# debugger_board.net
KiCad netlist of a schematic drawn in EAGLE
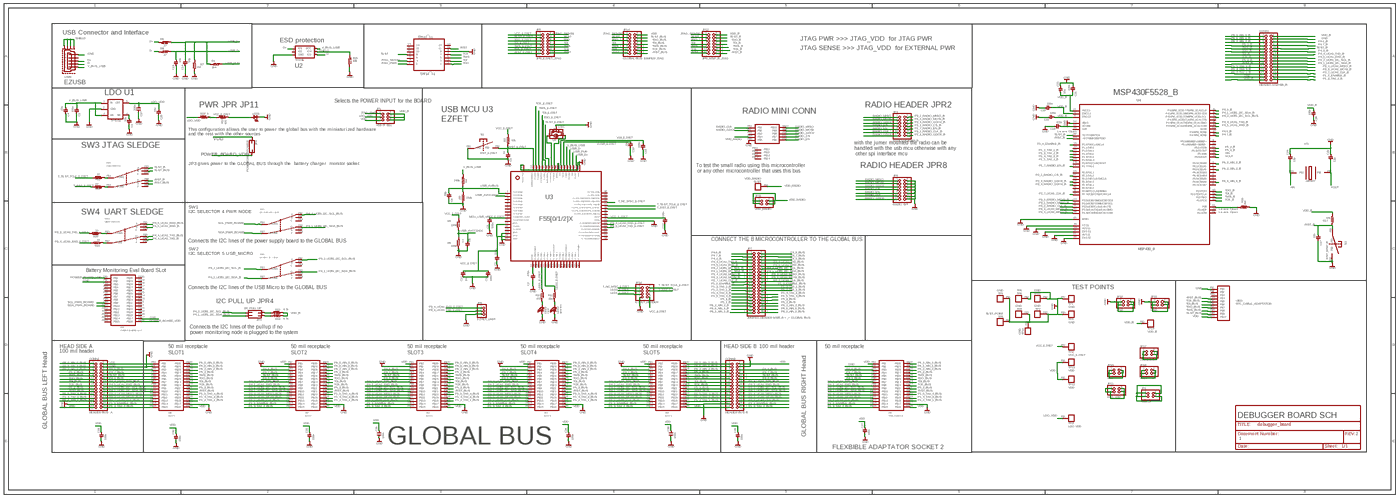
[diagram p0: schematic, sheet 1, overview]
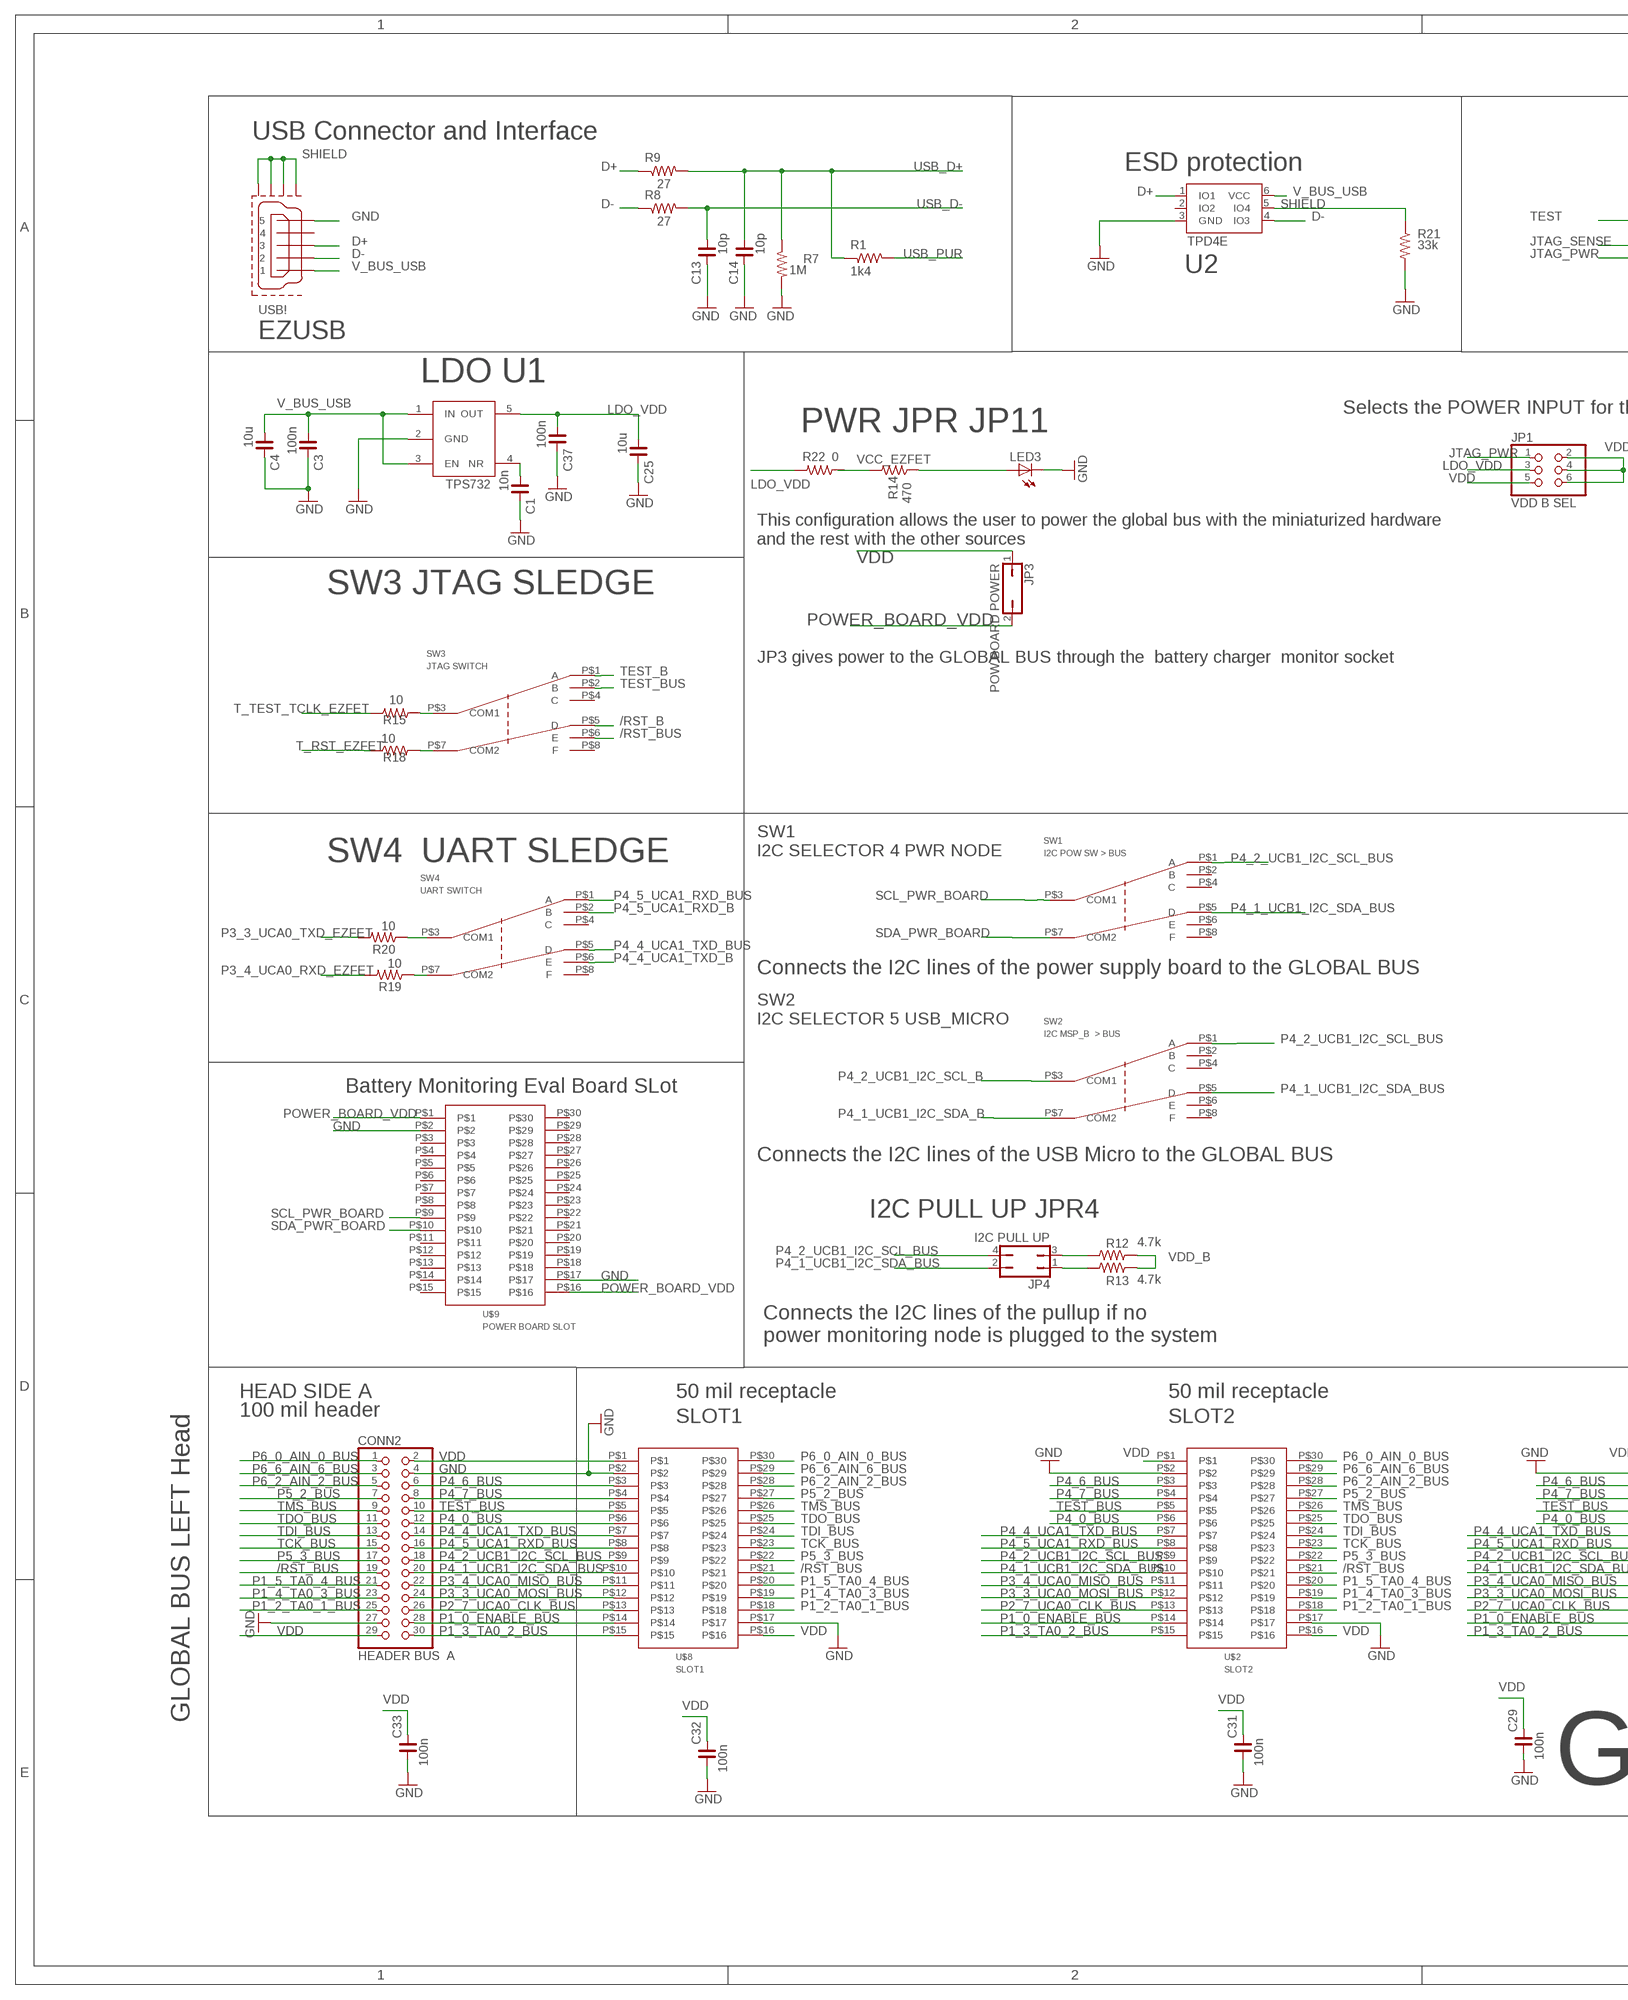
[diagram p1: schematic, sheet 1, part 1 of 4]
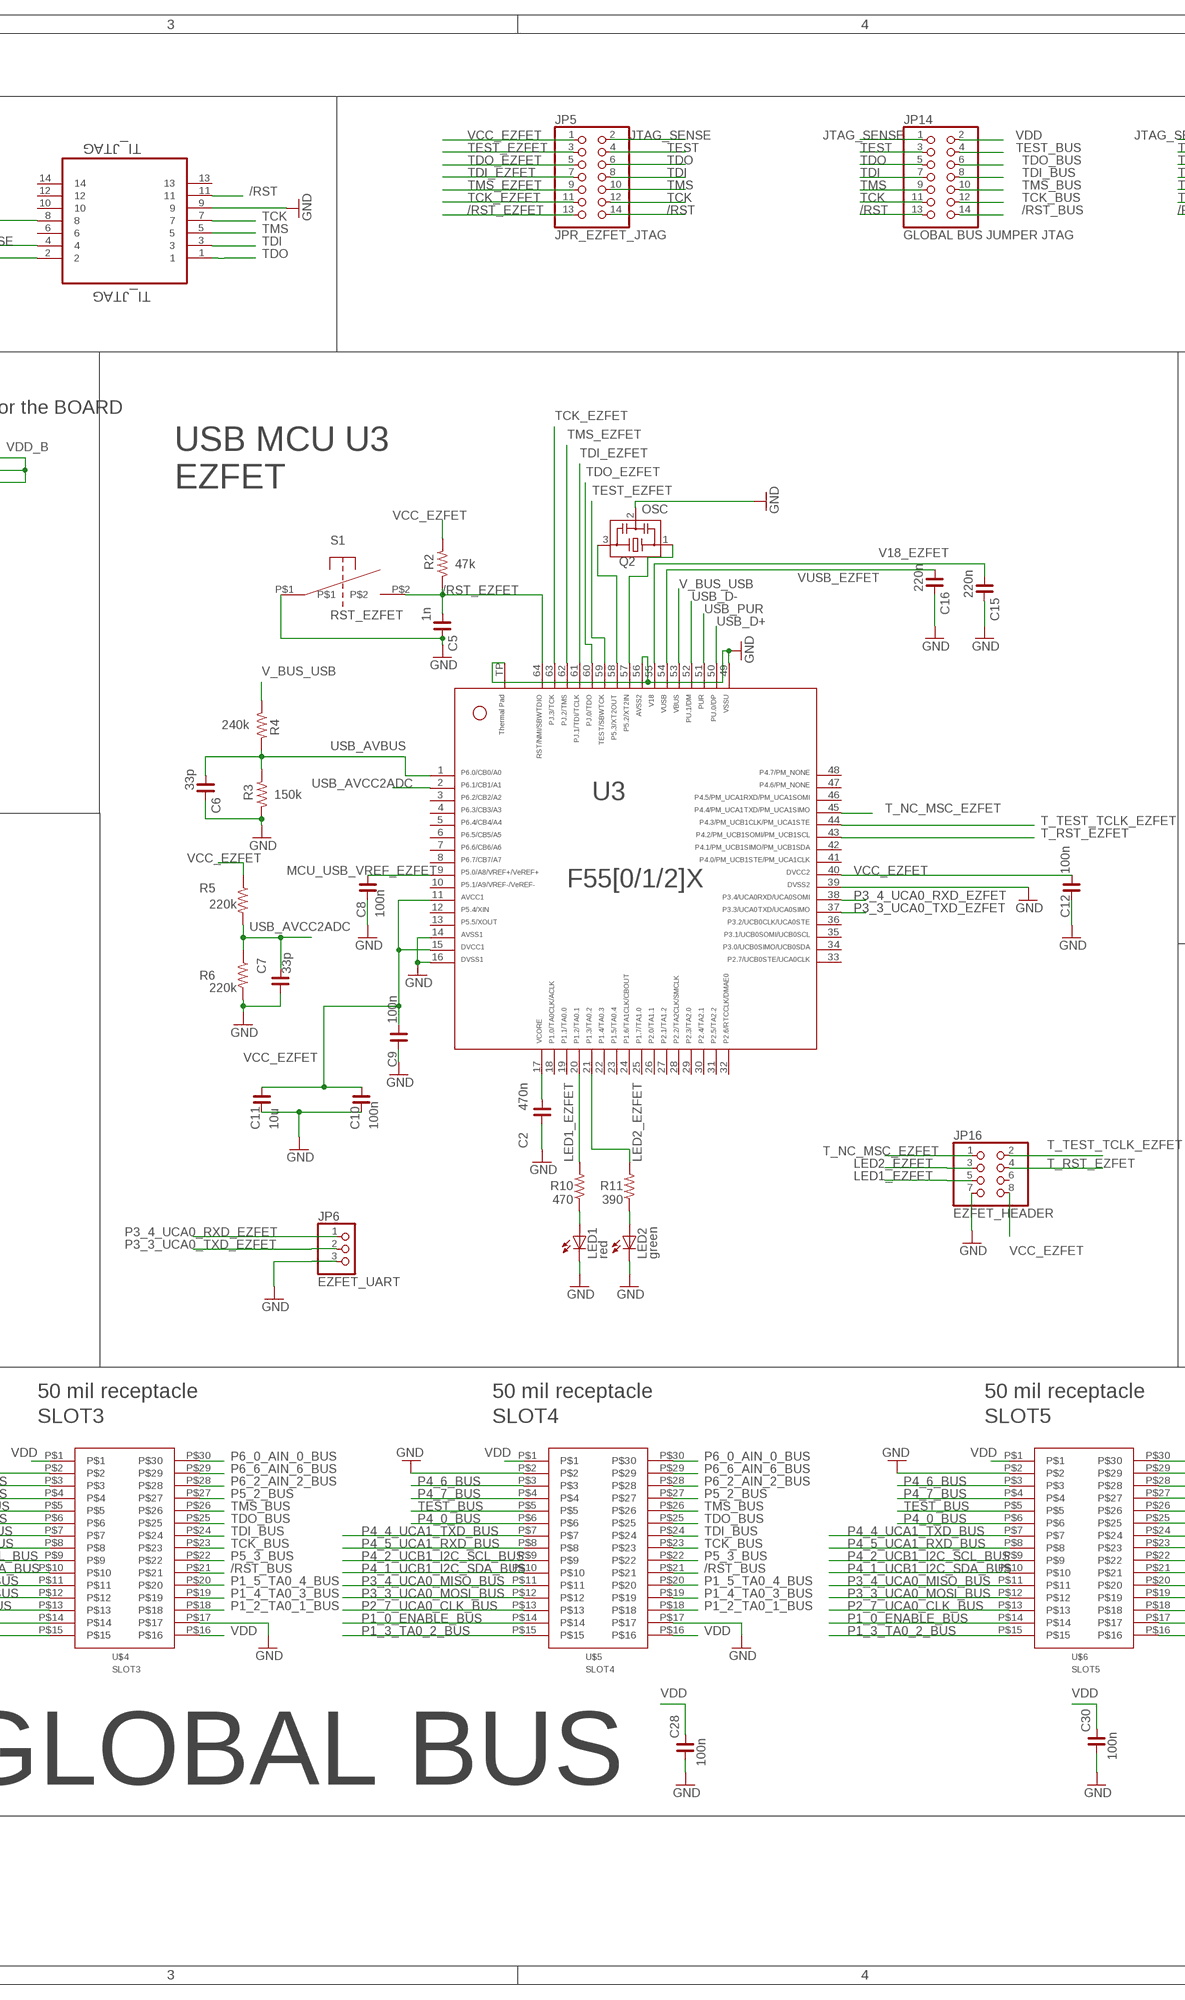
[diagram p2: schematic, sheet 1, part 2 of 4]
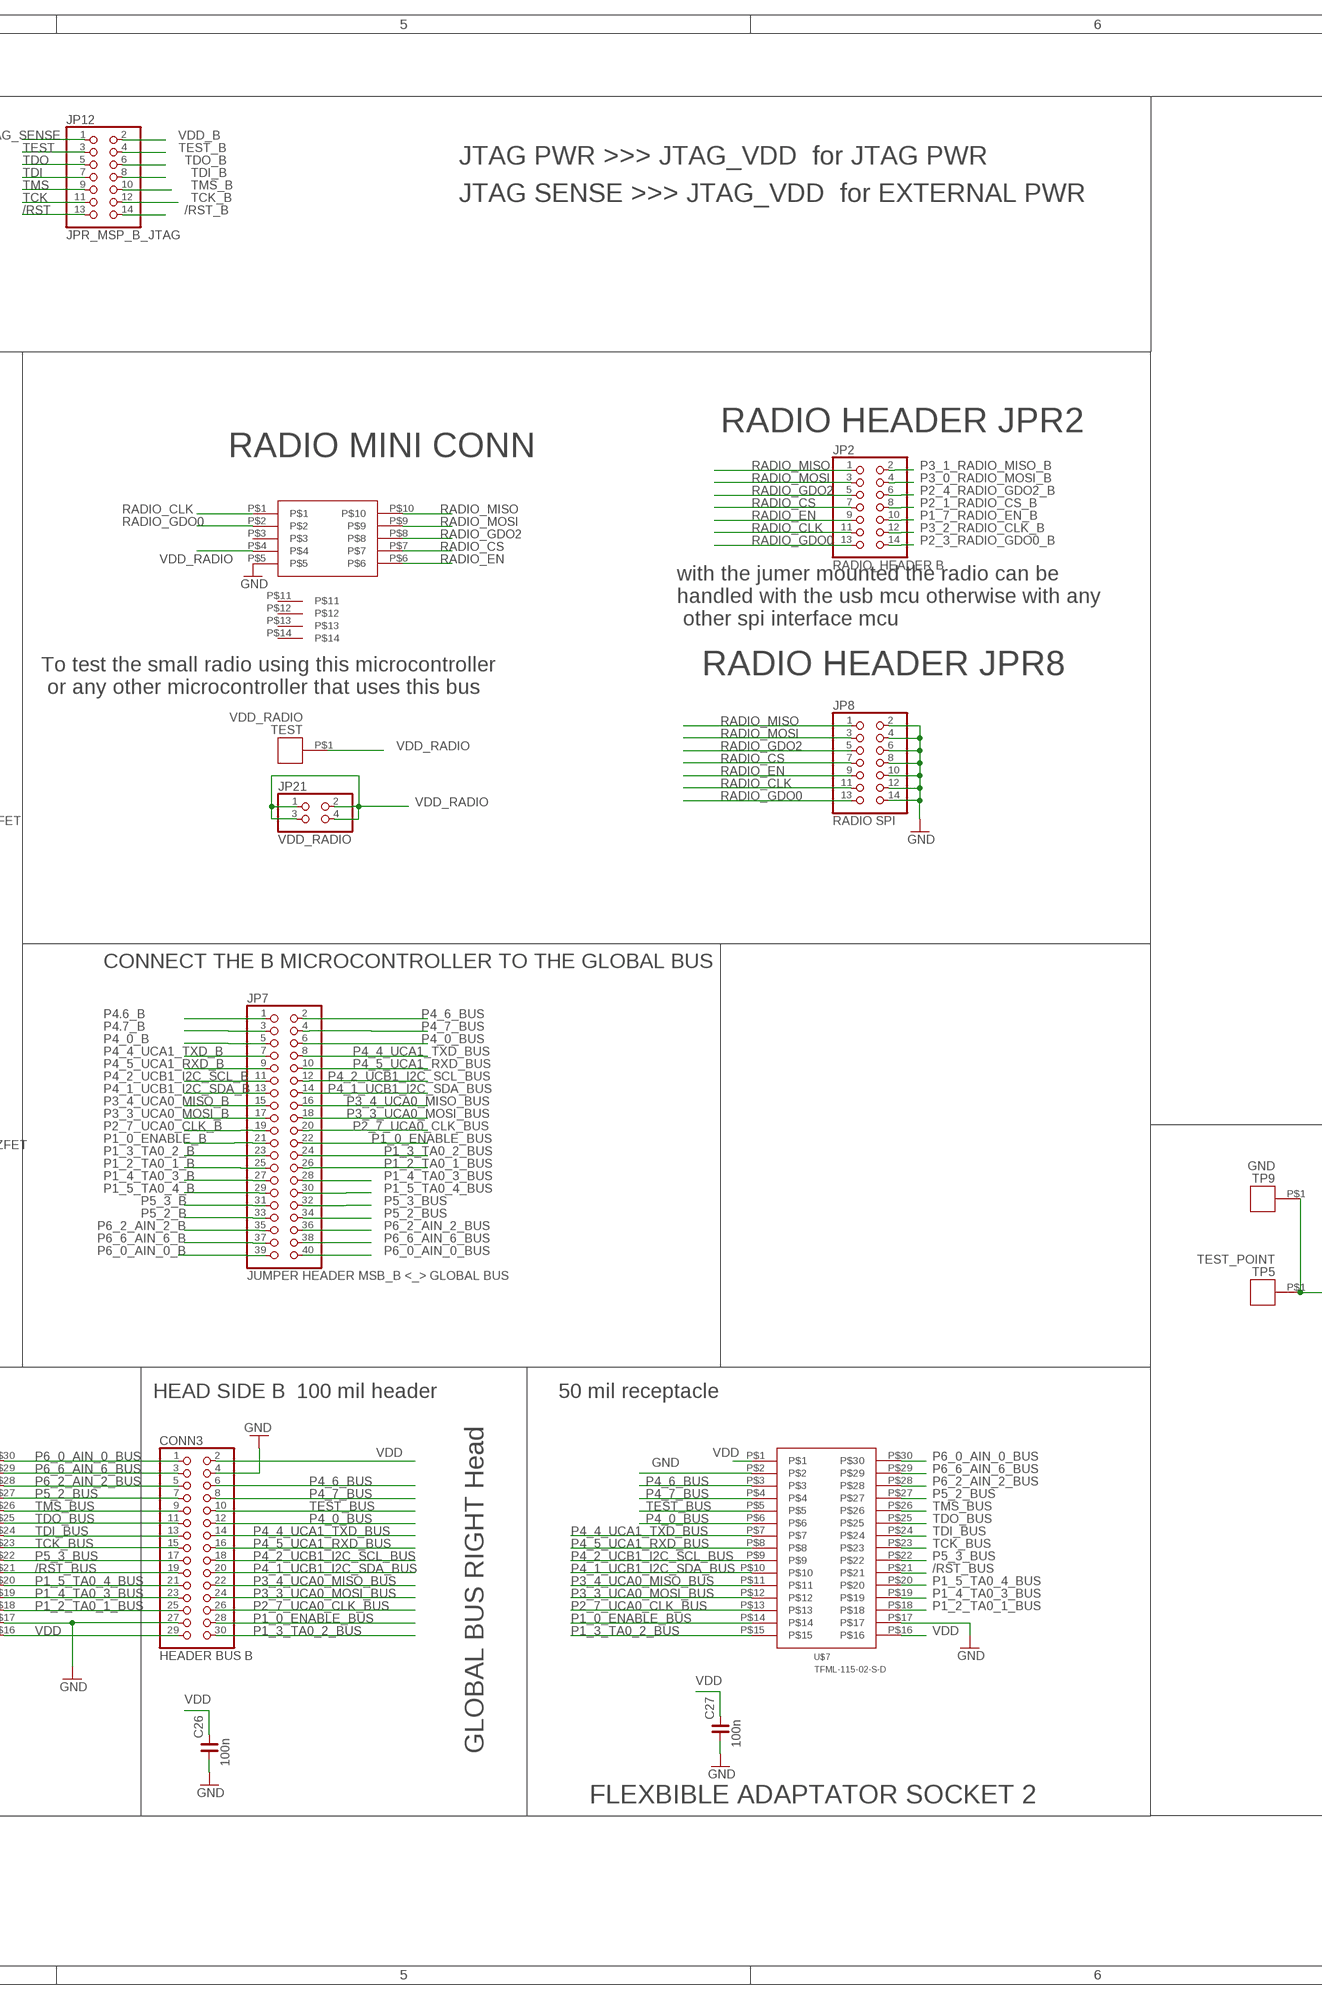
[diagram p3: schematic, sheet 1, part 3 of 4]
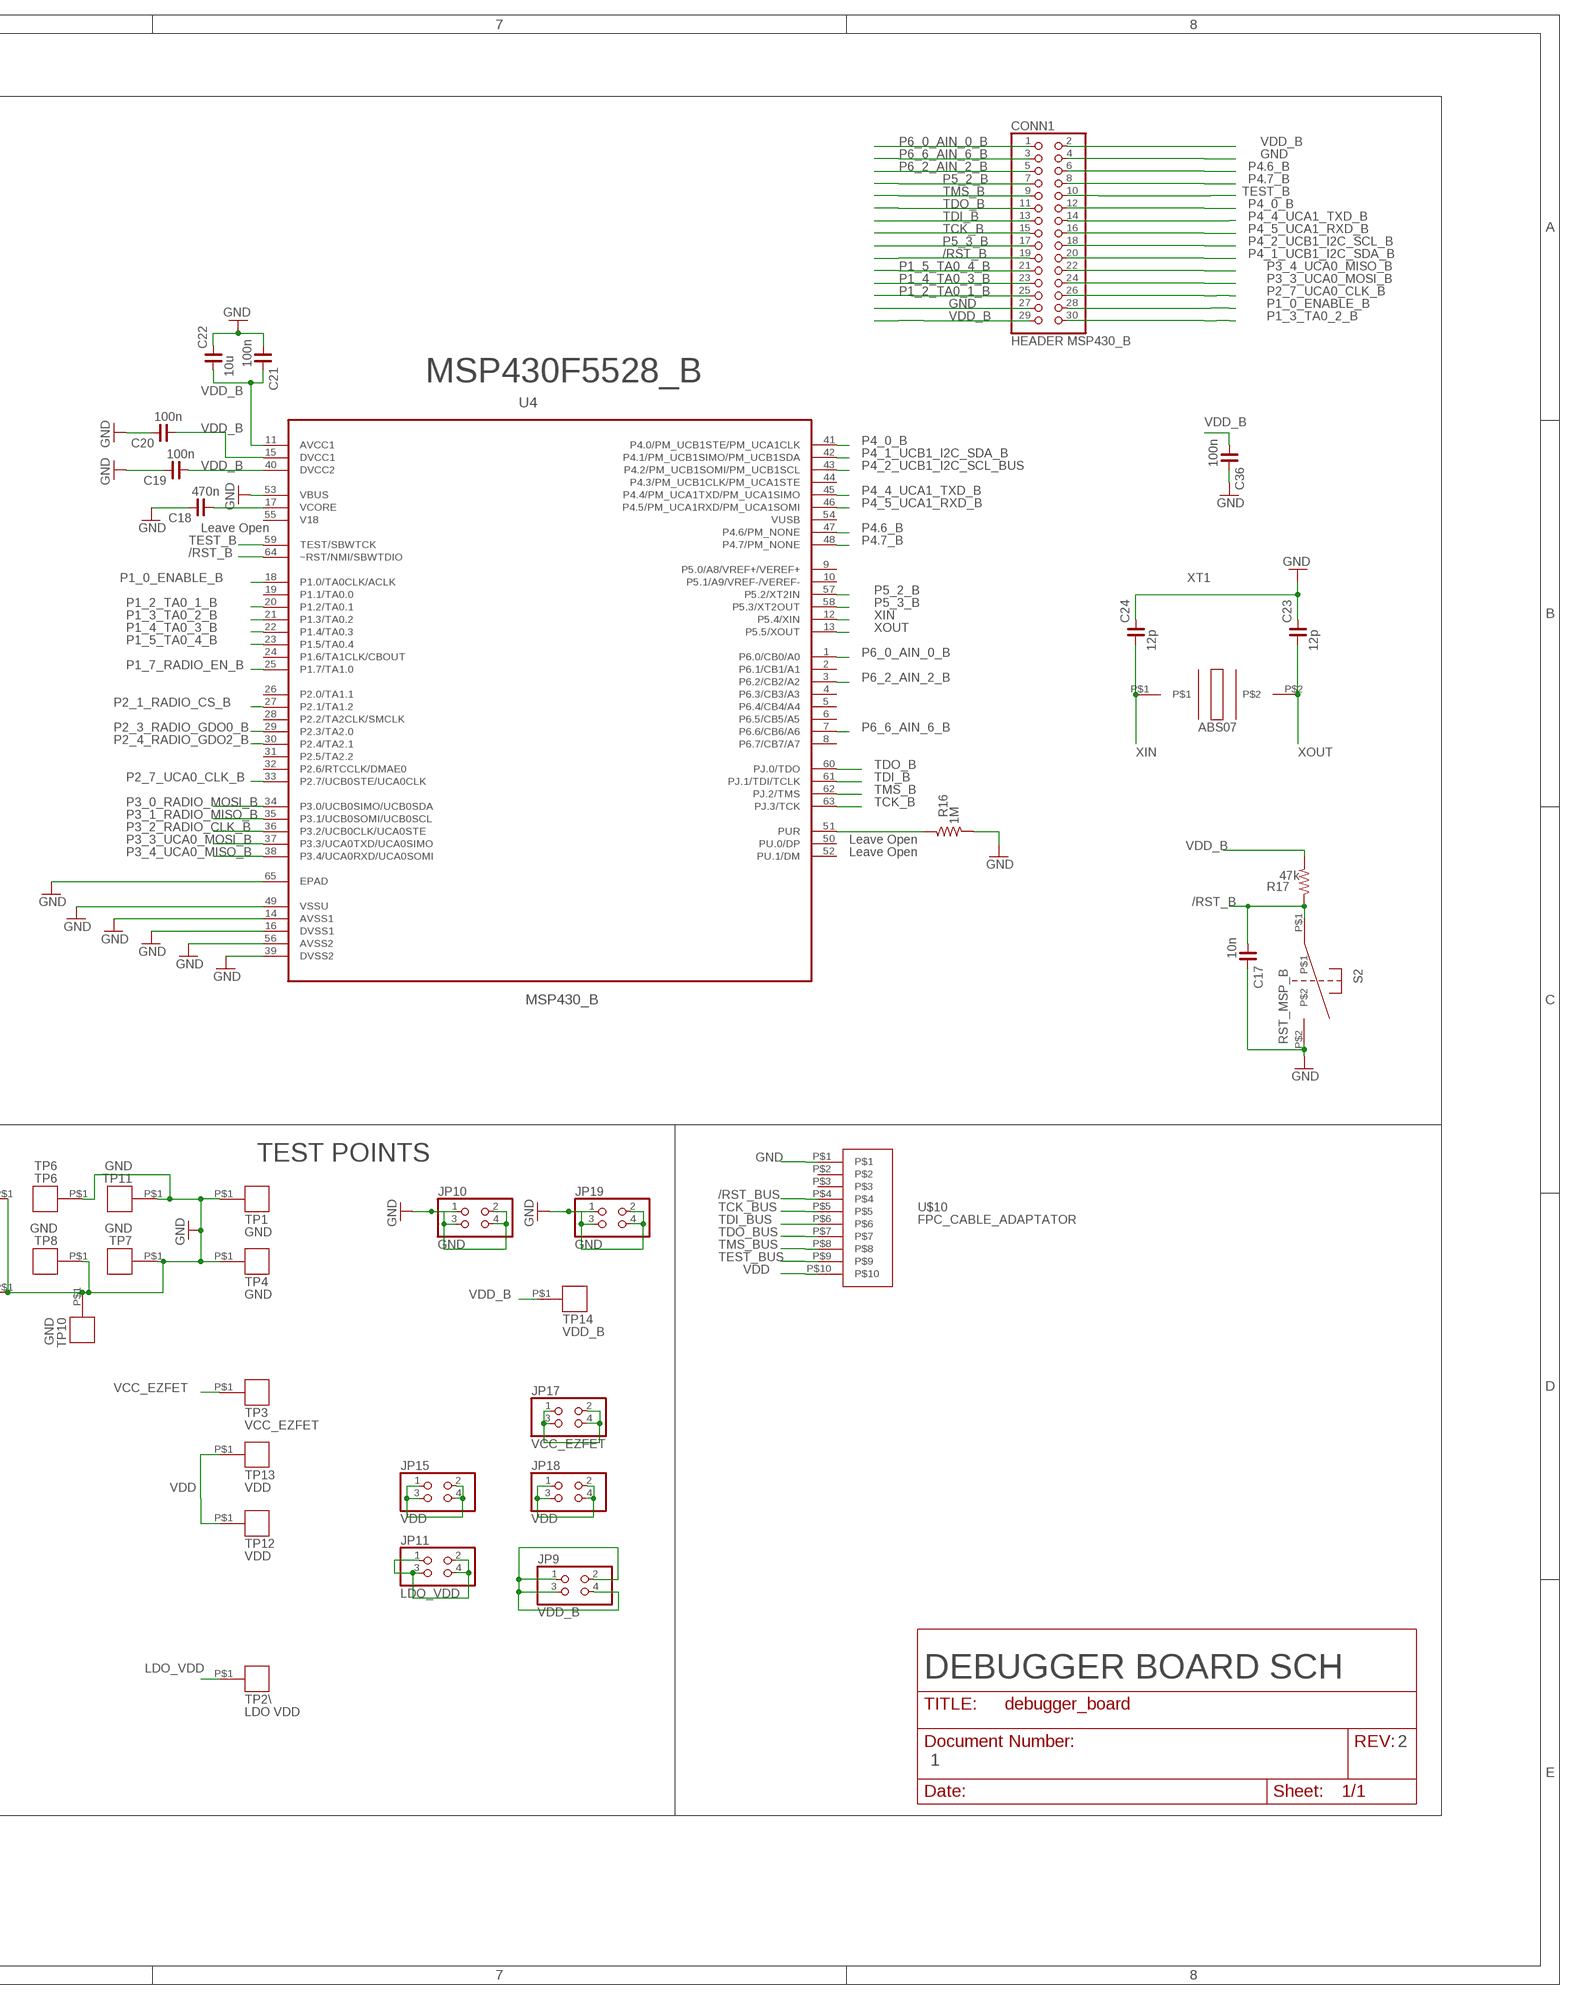
[diagram p4: schematic, sheet 1, part 4 of 4]

(export (version "E")
  (design (tool "Eeschema 10.0.6"))
  (components
    (comp (ref "C1")
      (value "10n")
      (footprint "eagle-import:C0603")
      (libsource (lib "eagle-import") (part "C_0603"))
    )
    (comp (ref "C2")
      (value "470n")
      (footprint "eagle-import:C0603")
      (libsource (lib "eagle-import") (part "C_0603"))
    )
    (comp (ref "C3")
      (value "100n")
      (footprint "eagle-import:C0603")
      (libsource (lib "eagle-import") (part "C_0603"))
    )
    (comp (ref "C4")
      (value "10u")
      (footprint "eagle-import:C0603")
      (libsource (lib "eagle-import") (part "C_0603"))
    )
    (comp (ref "C5")
      (value "1n")
      (footprint "eagle-import:C0603")
      (libsource (lib "eagle-import") (part "C_0603"))
    )
    (comp (ref "C6")
      (value "33p")
      (footprint "eagle-import:C0603")
      (libsource (lib "eagle-import") (part "C_0603"))
    )
    (comp (ref "C7")
      (value "33p")
      (footprint "eagle-import:C0603")
      (libsource (lib "eagle-import") (part "C_0603"))
    )
    (comp (ref "C8")
      (value "100n")
      (footprint "eagle-import:C0603")
      (libsource (lib "eagle-import") (part "C_0603"))
    )
    (comp (ref "C9")
      (value "100n")
      (footprint "eagle-import:C0603")
      (libsource (lib "eagle-import") (part "C_0603"))
    )
    (comp (ref "C10")
      (value "100n")
      (footprint "eagle-import:C0603")
      (libsource (lib "eagle-import") (part "C_0603"))
    )
    (comp (ref "C11")
      (value "10u")
      (footprint "eagle-import:C0603")
      (libsource (lib "eagle-import") (part "C_0603"))
    )
    (comp (ref "C12")
      (value "100n")
      (footprint "eagle-import:C0603")
      (libsource (lib "eagle-import") (part "C_0603"))
    )
    (comp (ref "C13")
      (value "10p")
      (footprint "eagle-import:C0603")
      (libsource (lib "eagle-import") (part "C_0603"))
    )
    (comp (ref "C14")
      (value "10p")
      (footprint "eagle-import:C0603")
      (libsource (lib "eagle-import") (part "C_0603"))
    )
    (comp (ref "C15")
      (value "220n")
      (footprint "eagle-import:C0603")
      (libsource (lib "eagle-import") (part "C_0603"))
    )
    (comp (ref "C16")
      (value "220n")
      (footprint "eagle-import:C0603")
      (libsource (lib "eagle-import") (part "C_0603"))
    )
    (comp (ref "C17")
      (value "10n")
      (footprint "eagle-import:C0603")
      (libsource (lib "eagle-import") (part "C_0603"))
    )
    (comp (ref "C18")
      (value "470n")
      (footprint "eagle-import:C0603")
      (libsource (lib "eagle-import") (part "C_0603"))
    )
    (comp (ref "C19")
      (value "100n")
      (footprint "eagle-import:C0603")
      (libsource (lib "eagle-import") (part "C_0603"))
    )
    (comp (ref "C20")
      (value "100n")
      (footprint "eagle-import:C0603")
      (libsource (lib "eagle-import") (part "C_0603"))
    )
    (comp (ref "C21")
      (value "100n")
      (footprint "eagle-import:C0603")
      (libsource (lib "eagle-import") (part "C_0603"))
    )
    (comp (ref "C22")
      (value "10u")
      (footprint "eagle-import:C0603")
      (libsource (lib "eagle-import") (part "C_0603"))
    )
    (comp (ref "C23")
      (value "12p")
      (footprint "eagle-import:C0603")
      (libsource (lib "eagle-import") (part "C_0603"))
    )
    (comp (ref "C24")
      (value "12p")
      (footprint "eagle-import:C0603")
      (libsource (lib "eagle-import") (part "C_0603"))
    )
    (comp (ref "C25")
      (value "10u")
      (footprint "eagle-import:C0603")
      (libsource (lib "eagle-import") (part "C_0603"))
    )
    (comp (ref "C26")
      (value "100n")
      (footprint "eagle-import:C0603")
      (libsource (lib "eagle-import") (part "C_0603"))
    )
    (comp (ref "C27")
      (value "100n")
      (footprint "eagle-import:C0603")
      (libsource (lib "eagle-import") (part "C_0603"))
    )
    (comp (ref "C28")
      (value "100n")
      (footprint "eagle-import:C0603")
      (libsource (lib "eagle-import") (part "C_0603"))
    )
    (comp (ref "C29")
      (value "100n")
      (footprint "eagle-import:C0603")
      (libsource (lib "eagle-import") (part "C_0603"))
    )
    (comp (ref "C30")
      (value "100n")
      (footprint "eagle-import:C0603")
      (libsource (lib "eagle-import") (part "C_0603"))
    )
    (comp (ref "C31")
      (value "100n")
      (footprint "eagle-import:C0603")
      (libsource (lib "eagle-import") (part "C_0603"))
    )
    (comp (ref "C32")
      (value "100n")
      (footprint "eagle-import:C0603")
      (libsource (lib "eagle-import") (part "C_0603"))
    )
    (comp (ref "C33")
      (value "100n")
      (footprint "eagle-import:C0603")
      (libsource (lib "eagle-import") (part "C_0603"))
    )
    (comp (ref "C36")
      (value "100n")
      (footprint "eagle-import:C0603")
      (libsource (lib "eagle-import") (part "C_0603"))
    )
    (comp (ref "C37")
      (value "100n")
      (footprint "eagle-import:C0603")
      (libsource (lib "eagle-import") (part "C_0603"))
    )
    (comp (ref "CONN1")
      (value "HEADER MSP430_B")
      (footprint "eagle-import:2X15")
      (libsource (lib "eagle-import") (part "PINHD-2X15"))
    )
    (comp (ref "CONN2")
      (value "HEADER BUS A")
      (footprint "eagle-import:2X15")
      (libsource (lib "eagle-import") (part "PINHD-2X15"))
    )
    (comp (ref "CONN3")
      (value "HEADER BUS B")
      (footprint "eagle-import:2X15")
      (libsource (lib "eagle-import") (part "PINHD-2X15"))
    )
    (comp (ref "EZUSB")
      (value "USB!")
      (footprint "eagle-import:UX60A-MB-5ST")
      (libsource (lib "eagle-import") (part "MINI-USB-SHIELD-UX60A-MB-5ST"))
    )
    (comp (ref "JP1")
      (value "VDD B SEL")
      (footprint "eagle-import:2X03")
      (libsource (lib "eagle-import") (part "PINHD-2X3"))
    )
    (comp (ref "JP2")
      (value "RADIO_HEADER B")
      (footprint "eagle-import:2X07")
      (libsource (lib "eagle-import") (part "PINHD-2X7"))
    )
    (comp (ref "JP3")
      (value "POW BOARD POWER")
      (footprint "eagle-import:JP1")
      (libsource (lib "eagle-import") (part "JP1Q"))
    )
    (comp (ref "JP4")
      (value "I2C PULL UP")
      (footprint "eagle-import:JP2Q")
      (libsource (lib "eagle-import") (part "JP2Q"))
    )
    (comp (ref "JP5")
      (value "JPR_EZFET_JTAG")
      (footprint "eagle-import:2X07")
      (libsource (lib "eagle-import") (part "PINHD-2X7"))
    )
    (comp (ref "JP6")
      (value "EZFET_UART")
      (footprint "eagle-import:1X03")
      (libsource (lib "eagle-import") (part "PINHD-1X3"))
    )
    (comp (ref "JP7")
      (value "JUMPER HEADER MSB_B <_> GLOBAL BUS")
      (footprint "eagle-import:2X20")
      (libsource (lib "eagle-import") (part "PINHD-2X20"))
    )
    (comp (ref "JP8")
      (value "RADIO SPI")
      (footprint "eagle-import:2X07")
      (libsource (lib "eagle-import") (part "PINHD-2X7"))
    )
    (comp (ref "JP9")
      (value "VDD_B")
      (footprint "eagle-import:2X02")
      (libsource (lib "eagle-import") (part "PINHD-2X2"))
    )
    (comp (ref "JP10")
      (value "GND")
      (footprint "eagle-import:2X02")
      (libsource (lib "eagle-import") (part "PINHD-2X2"))
    )
    (comp (ref "JP11")
      (value "LDO_VDD")
      (footprint "eagle-import:2X02")
      (libsource (lib "eagle-import") (part "PINHD-2X2"))
    )
    (comp (ref "JP12")
      (value "JPR_MSP_B_JTAG")
      (footprint "eagle-import:2X07")
      (libsource (lib "eagle-import") (part "PINHD-2X7"))
    )
    (comp (ref "JP14")
      (value "GLOBAL BUS JUMPER JTAG")
      (footprint "eagle-import:2X07")
      (libsource (lib "eagle-import") (part "PINHD-2X7"))
    )
    (comp (ref "JP15")
      (value "VDD")
      (footprint "eagle-import:2X02")
      (libsource (lib "eagle-import") (part "PINHD-2X2"))
    )
    (comp (ref "JP16")
      (value "EZFET_HEADER")
      (footprint "eagle-import:2X04")
      (libsource (lib "eagle-import") (part "PINHD-2X4"))
    )
    (comp (ref "JP17")
      (value "VCC_EZFET")
      (footprint "eagle-import:2X02")
      (libsource (lib "eagle-import") (part "PINHD-2X2"))
    )
    (comp (ref "JP18")
      (value "VDD")
      (footprint "eagle-import:2X02")
      (libsource (lib "eagle-import") (part "PINHD-2X2"))
    )
    (comp (ref "JP19")
      (value "GND")
      (footprint "eagle-import:2X02")
      (libsource (lib "eagle-import") (part "PINHD-2X2"))
    )
    (comp (ref "JP21")
      (value "VDD_RADIO")
      (footprint "eagle-import:2X02")
      (libsource (lib "eagle-import") (part "PINHD-2X2"))
    )
    (comp (ref "LED1")
      (value "red")
      (footprint "eagle-import:CHIP-LED0603")
      (libsource (lib "eagle-import") (part "LEDCHIP-LED0603"))
    )
    (comp (ref "LED2")
      (value "green")
      (footprint "eagle-import:CHIP-LED0603")
      (libsource (lib "eagle-import") (part "LEDCHIP-LED0603"))
    )
    (comp (ref "LED3")
      (value "LEDCHIP-LED0603")
      (footprint "eagle-import:CHIP-LED0603")
      (libsource (lib "eagle-import") (part "LEDCHIP-LED0603"))
    )
    (comp (ref "Q2")
      (value "OSC")
      (footprint "eagle-import:CSTCR6M")
      (fields (field (name "MPN") "CSTCR6M00G53-R0"))
      (libsource (lib "eagle-import") (part "CSTCR6M00G53Z"))
    )
    (comp (ref "R1")
      (value "1k4")
      (footprint "eagle-import:R0603")
      (libsource (lib "eagle-import") (part "R_0603"))
    )
    (comp (ref "R2")
      (value "47k")
      (footprint "eagle-import:R0603")
      (libsource (lib "eagle-import") (part "R_0603"))
    )
    (comp (ref "R3")
      (value "150k")
      (footprint "eagle-import:R0603")
      (libsource (lib "eagle-import") (part "R_0603"))
    )
    (comp (ref "R4")
      (value "240k")
      (footprint "eagle-import:R0603")
      (libsource (lib "eagle-import") (part "R_0603"))
    )
    (comp (ref "R5")
      (value "220k")
      (footprint "eagle-import:R0603")
      (libsource (lib "eagle-import") (part "R_0603"))
    )
    (comp (ref "R6")
      (value "220k")
      (footprint "eagle-import:R0603")
      (libsource (lib "eagle-import") (part "R_0603"))
    )
    (comp (ref "R7")
      (value "1M")
      (footprint "eagle-import:R0603")
      (libsource (lib "eagle-import") (part "R_0603"))
    )
    (comp (ref "R8")
      (value "27")
      (footprint "eagle-import:R0603")
      (libsource (lib "eagle-import") (part "R_0603"))
    )
    (comp (ref "R9")
      (value "27")
      (footprint "eagle-import:R0603")
      (libsource (lib "eagle-import") (part "R_0603"))
    )
    (comp (ref "R10")
      (value "470")
      (footprint "eagle-import:R0603")
      (libsource (lib "eagle-import") (part "R_0603"))
    )
    (comp (ref "R11")
      (value "390")
      (footprint "eagle-import:R0603")
      (libsource (lib "eagle-import") (part "R_0603"))
    )
    (comp (ref "R12")
      (value "4.7k")
      (footprint "eagle-import:R0603")
      (libsource (lib "eagle-import") (part "R_0603"))
    )
    (comp (ref "R13")
      (value "4.7k")
      (footprint "eagle-import:R0603")
      (libsource (lib "eagle-import") (part "R_0603"))
    )
    (comp (ref "R14")
      (value "470")
      (footprint "eagle-import:R0603")
      (libsource (lib "eagle-import") (part "R_0603"))
    )
    (comp (ref "R15")
      (value "10")
      (footprint "eagle-import:R0603")
      (libsource (lib "eagle-import") (part "R_0603"))
    )
    (comp (ref "R16")
      (value "1M")
      (footprint "eagle-import:R0603")
      (libsource (lib "eagle-import") (part "R_0603"))
    )
    (comp (ref "R17")
      (value "47k")
      (footprint "eagle-import:R0603")
      (libsource (lib "eagle-import") (part "R_0603"))
    )
    (comp (ref "R18")
      (value "10")
      (footprint "eagle-import:R0603")
      (libsource (lib "eagle-import") (part "R_0603"))
    )
    (comp (ref "R19")
      (value "10")
      (footprint "eagle-import:R0603")
      (libsource (lib "eagle-import") (part "R_0603"))
    )
    (comp (ref "R20")
      (value "10")
      (footprint "eagle-import:R0603")
      (libsource (lib "eagle-import") (part "R_0603"))
    )
    (comp (ref "R21")
      (value "33k")
      (footprint "eagle-import:R0603")
      (libsource (lib "eagle-import") (part "R_0603"))
    )
    (comp (ref "R22")
      (value "0")
      (footprint "eagle-import:R1206")
      (libsource (lib "eagle-import") (part "R_1206"))
    )
    (comp (ref "RADIO_CONN")
      (value "RADIO")
      (footprint "eagle-import:559099872_2X5_PLUG")
      (libsource (lib "eagle-import") (part "559099872_2X5_PLUG"))
    )
    (comp (ref "S1")
      (value "RST_EZFET")
      (footprint "eagle-import:EVQ_11_TH")
      (libsource (lib "eagle-import") (part "PUSH_BOT"))
    )
    (comp (ref "S2")
      (value "RST_MSP_B")
      (footprint "eagle-import:EVQ_11_TH")
      (libsource (lib "eagle-import") (part "PUSH_BOT"))
    )
    (comp (ref "SW1")
      (value "I2C POW SW > BUS")
      (footprint "eagle-import:CL-SB-23B-02")
      (libsource (lib "eagle-import") (part "SWITCH_SLEDGE_3POS"))
    )
    (comp (ref "SW2")
      (value "I2C MSP_B > BUS")
      (footprint "eagle-import:CL-SB-23B-02")
      (libsource (lib "eagle-import") (part "SWITCH_SLEDGE_3POS"))
    )
    (comp (ref "SW3")
      (value "JTAG SWITCH")
      (footprint "eagle-import:CL-SB-23B-02")
      (libsource (lib "eagle-import") (part "SWITCH_SLEDGE_3POS"))
    )
    (comp (ref "SW4")
      (value "UART SWITCH")
      (footprint "eagle-import:CL-SB-23B-02")
      (libsource (lib "eagle-import") (part "SWITCH_SLEDGE_3POS"))
    )
    (comp (ref "TEST")
      (value "VDD_RADIO")
      (footprint "eagle-import:5019_PAD")
      (libsource (lib "eagle-import") (part "TEST_POINT"))
    )
    (comp (ref "TI_JTAG")
      (value "TI_JTAG")
      (footprint "eagle-import:TYCO_5103308-2")
      (fields (field (name "MPN") "5103308-2"))
      (libsource (lib "eagle-import") (part "5103308-2"))
    )
    (comp (ref "TP1")
      (value "GND")
      (footprint "eagle-import:5019_PAD")
      (libsource (lib "eagle-import") (part "TEST_POINT"))
    )
    (comp (ref "TP2\\")
      (value "LDO VDD")
      (footprint "eagle-import:5019_PAD")
      (libsource (lib "eagle-import") (part "TEST_POINT"))
    )
    (comp (ref "TP3")
      (value "VCC_EZFET")
      (footprint "eagle-import:5019_PAD")
      (libsource (lib "eagle-import") (part "TEST_POINT"))
    )
    (comp (ref "TP4")
      (value "GND")
      (footprint "eagle-import:5019_PAD")
      (libsource (lib "eagle-import") (part "TEST_POINT"))
    )
    (comp (ref "TP5")
      (value "TEST_POINT")
      (footprint "eagle-import:5019_PAD")
      (libsource (lib "eagle-import") (part "TEST_POINT"))
    )
    (comp (ref "TP6")
      (value "TP6")
      (footprint "eagle-import:5019_PAD")
      (libsource (lib "eagle-import") (part "TEST_POINT"))
    )
    (comp (ref "TP7")
      (value "GND")
      (footprint "eagle-import:5019_PAD")
      (libsource (lib "eagle-import") (part "TEST_POINT"))
    )
    (comp (ref "TP8")
      (value "GND")
      (footprint "eagle-import:5019_PAD")
      (libsource (lib "eagle-import") (part "TEST_POINT"))
    )
    (comp (ref "TP9")
      (value "GND")
      (footprint "eagle-import:5019_PAD")
      (libsource (lib "eagle-import") (part "TEST_POINT"))
    )
    (comp (ref "TP10")
      (value "GND")
      (footprint "eagle-import:5019_PAD")
      (libsource (lib "eagle-import") (part "TEST_POINT"))
    )
    (comp (ref "TP11")
      (value "GND")
      (footprint "eagle-import:5019_PAD")
      (libsource (lib "eagle-import") (part "TEST_POINT"))
    )
    (comp (ref "TP12")
      (value "VDD")
      (footprint "eagle-import:5019_PAD")
      (libsource (lib "eagle-import") (part "TEST_POINT"))
    )
    (comp (ref "TP13")
      (value "VDD")
      (footprint "eagle-import:5019_PAD")
      (libsource (lib "eagle-import") (part "TEST_POINT"))
    )
    (comp (ref "TP14")
      (value "VDD_B")
      (footprint "eagle-import:5019_PAD")
      (libsource (lib "eagle-import") (part "TEST_POINT"))
    )
    (comp (ref "U$2")
      (value "SLOT2")
      (footprint "eagle-import:TFML-115-02-S-D")
      (libsource (lib "eagle-import") (part "TFML-115-02-S-D"))
    )
    (comp (ref "U$4")
      (value "SLOT3")
      (footprint "eagle-import:TFML-115-02-S-D")
      (libsource (lib "eagle-import") (part "TFML-115-02-S-D"))
    )
    (comp (ref "U$5")
      (value "SLOT4")
      (footprint "eagle-import:TFML-115-02-S-D")
      (libsource (lib "eagle-import") (part "TFML-115-02-S-D"))
    )
    (comp (ref "U$6")
      (value "SLOT5")
      (footprint "eagle-import:TFML-115-02-S-D")
      (libsource (lib "eagle-import") (part "TFML-115-02-S-D"))
    )
    (comp (ref "U$7")
      (value "TFML-115-02-S-D")
      (footprint "eagle-import:TFML-115-02-S-D")
      (libsource (lib "eagle-import") (part "TFML-115-02-S-D"))
    )
    (comp (ref "U$8")
      (value "SLOT1")
      (footprint "eagle-import:TFML-115-02-S-D")
      (libsource (lib "eagle-import") (part "TFML-115-02-S-D"))
    )
    (comp (ref "U$9")
      (value "POWER BOARD SLOT")
      (footprint "eagle-import:TFML-115-02-S-D")
      (libsource (lib "eagle-import") (part "TFML-115-02-S-D"))
    )
    (comp (ref "U$10")
      (value "FPC_CABLE_ADAPTATOR")
      (footprint "eagle-import:FPC_FFC")
      (libsource (lib "eagle-import") (part "CABLE_ADAPTATOR"))
    )
    (comp (ref "U$16")
      (value "OSC32K")
      (footprint "eagle-import:ABS07")
      (libsource (lib "eagle-import") (part "OSC32K"))
    )
    (comp (ref "U1")
      (value "TPS73233")
      (footprint "eagle-import:SOT23")
      (libsource (lib "eagle-import") (part "TPS732XX"))
    )
    (comp (ref "U2")
      (value "TPD4E")
      (footprint "eagle-import:SON(DRY)6")
      (libsource (lib "eagle-import") (part "TPD4E004"))
    )
    (comp (ref "U3")
      (value "USB_EZFET")
      (footprint "eagle-import:RGC64")
      (libsource (lib "eagle-import") (part "F55[0/1/2]X---RGC64"))
    )
    (comp (ref "U4")
      (value "MSP430_B")
      (footprint "eagle-import:QFN50P900X900X100-65N")
      (fields (field (name "MPN") "MSP430F5528IRGCT"))
      (libsource (lib "eagle-import") (part "MSP430F5528IRGCT"))
    )
  )
  (nets
    (net (code "1") (name "/D+") (class "Default")
      (node (ref "EZUSB") (pin "3") (pinfunction "3_3") (pintype "input"))
      (node (ref "R9") (pin "1") (pinfunction "1_1") (pintype "passive"))
      (node (ref "U2") (pin "1") (pinfunction "IO1_1") (pintype "bidirectional"))
    )
    (net (code "2") (name "/D-") (class "Default")
      (node (ref "EZUSB") (pin "2") (pinfunction "2_2") (pintype "input"))
      (node (ref "R8") (pin "1") (pinfunction "1_1") (pintype "passive"))
      (node (ref "U2") (pin "4") (pinfunction "IO3_4") (pintype "bidirectional"))
    )
    (net (code "3") (name "/JTAG_PWR") (class "Default")
      (node (ref "JP1") (pin "1") (pinfunction "1_1") (pintype "passive"))
      (node (ref "TI_JTAG") (pin "2") (pinfunction "2_2") (pintype "passive"))
    )
    (net (code "4") (name "/JTAG_SENSE") (class "Default")
      (node (ref "JP12") (pin "1") (pinfunction "1_1") (pintype "passive"))
      (node (ref "JP14") (pin "1") (pinfunction "1_1") (pintype "passive"))
      (node (ref "JP5") (pin "2") (pinfunction "2_2") (pintype "passive"))
      (node (ref "TI_JTAG") (pin "4") (pinfunction "4_4") (pintype "passive"))
    )
    (net (code "5") (name "/LDO_VDD") (class "Default")
      (node (ref "C25") (pin "1") (pinfunction "1_1") (pintype "passive"))
      (node (ref "C37") (pin "1") (pinfunction "1_1") (pintype "passive"))
      (node (ref "JP1") (pin "3") (pinfunction "3_3") (pintype "passive"))
      (node (ref "JP11") (pin "1") (pinfunction "1_1") (pintype "passive"))
      (node (ref "JP11") (pin "2") (pinfunction "2_2") (pintype "passive"))
      (node (ref "JP11") (pin "3") (pinfunction "3_3") (pintype "passive"))
      (node (ref "JP11") (pin "4") (pinfunction "4_4") (pintype "passive"))
      (node (ref "R22") (pin "2") (pinfunction "2_2") (pintype "passive"))
      (node (ref "TP2\\") (pin "P$1") (pinfunction "P$1_P$1") (pintype "bidirectional"))
      (node (ref "U1") (pin "5") (pinfunction "OUT_5") (pintype "bidirectional"))
    )
    (net (code "6") (name "/LED1_EZFET") (class "Default")
      (node (ref "JP16") (pin "5") (pinfunction "5_5") (pintype "passive"))
      (node (ref "R10") (pin "2") (pinfunction "2_2") (pintype "passive"))
      (node (ref "U3") (pin "20") (pinfunction "20_20") (pintype "bidirectional"))
    )
    (net (code "7") (name "/LED2_EZFET") (class "Default")
      (node (ref "JP16") (pin "3") (pinfunction "3_3") (pintype "passive"))
      (node (ref "R11") (pin "2") (pinfunction "2_2") (pintype "passive"))
      (node (ref "U3") (pin "21") (pinfunction "21_21") (pintype "bidirectional"))
    )
    (net (code "8") (name "/MCU_USB_VREF_EZFET") (class "Default")
      (node (ref "C8") (pin "2") (pinfunction "2_2") (pintype "passive"))
      (node (ref "U3") (pin "9") (pinfunction "9_9") (pintype "output"))
    )
    (net (code "9") (name "/P1_0_ENABLE_B") (class "Default")
      (node (ref "CONN1") (pin "28") (pinfunction "28_28") (pintype "passive"))
      (node (ref "JP7") (pin "21") (pinfunction "21_21") (pintype "passive"))
      (node (ref "U4") (pin "18") (pinfunction "P1.0/TA0CLK/ACLK_18") (pintype "bidirectional"))
    )
    (net (code "10") (name "/P1_0_ENABLE_BUS") (class "Default")
      (node (ref "CONN2") (pin "28") (pinfunction "28_28") (pintype "passive"))
      (node (ref "CONN3") (pin "28") (pinfunction "28_28") (pintype "passive"))
      (node (ref "JP7") (pin "22") (pinfunction "22_22") (pintype "passive"))
      (node (ref "U$2") (pin "P$14") (pinfunction "P$14_P$14") (pintype "bidirectional"))
      (node (ref "U$4") (pin "P$14") (pinfunction "P$14_P$14") (pintype "bidirectional"))
      (node (ref "U$5") (pin "P$14") (pinfunction "P$14_P$14") (pintype "bidirectional"))
      (node (ref "U$6") (pin "P$14") (pinfunction "P$14_P$14") (pintype "bidirectional"))
      (node (ref "U$7") (pin "P$14") (pinfunction "P$14_P$14") (pintype "bidirectional"))
      (node (ref "U$8") (pin "P$14") (pinfunction "P$14_P$14") (pintype "bidirectional"))
    )
    (net (code "11") (name "/P1_2_TA0_1_B") (class "Default")
      (node (ref "CONN1") (pin "25") (pinfunction "25_25") (pintype "passive"))
      (node (ref "JP7") (pin "25") (pinfunction "25_25") (pintype "passive"))
      (node (ref "U4") (pin "20") (pinfunction "P1.2/TA0.1_20") (pintype "bidirectional"))
    )
    (net (code "12") (name "/P1_2_TA0_1_BUS") (class "Default")
      (node (ref "CONN2") (pin "25") (pinfunction "25_25") (pintype "passive"))
      (node (ref "CONN3") (pin "25") (pinfunction "25_25") (pintype "passive"))
      (node (ref "JP7") (pin "26") (pinfunction "26_26") (pintype "passive"))
      (node (ref "U$2") (pin "P$18") (pinfunction "P$18_P$18") (pintype "bidirectional"))
      (node (ref "U$4") (pin "P$18") (pinfunction "P$18_P$18") (pintype "bidirectional"))
      (node (ref "U$5") (pin "P$18") (pinfunction "P$18_P$18") (pintype "bidirectional"))
      (node (ref "U$6") (pin "P$18") (pinfunction "P$18_P$18") (pintype "bidirectional"))
      (node (ref "U$7") (pin "P$18") (pinfunction "P$18_P$18") (pintype "bidirectional"))
      (node (ref "U$8") (pin "P$18") (pinfunction "P$18_P$18") (pintype "bidirectional"))
    )
    (net (code "13") (name "/P1_3_TA0_2_B") (class "Default")
      (node (ref "CONN1") (pin "30") (pinfunction "30_30") (pintype "passive"))
      (node (ref "JP7") (pin "23") (pinfunction "23_23") (pintype "passive"))
      (node (ref "U4") (pin "21") (pinfunction "P1.3/TA0.2_21") (pintype "bidirectional"))
    )
    (net (code "14") (name "/P1_3_TA0_2_BUS") (class "Default")
      (node (ref "CONN2") (pin "30") (pinfunction "30_30") (pintype "passive"))
      (node (ref "CONN3") (pin "30") (pinfunction "30_30") (pintype "passive"))
      (node (ref "JP7") (pin "24") (pinfunction "24_24") (pintype "passive"))
      (node (ref "U$2") (pin "P$15") (pinfunction "P$15_P$15") (pintype "bidirectional"))
      (node (ref "U$4") (pin "P$15") (pinfunction "P$15_P$15") (pintype "bidirectional"))
      (node (ref "U$5") (pin "P$15") (pinfunction "P$15_P$15") (pintype "bidirectional"))
      (node (ref "U$6") (pin "P$15") (pinfunction "P$15_P$15") (pintype "bidirectional"))
      (node (ref "U$7") (pin "P$15") (pinfunction "P$15_P$15") (pintype "bidirectional"))
      (node (ref "U$8") (pin "P$15") (pinfunction "P$15_P$15") (pintype "bidirectional"))
    )
    (net (code "15") (name "/P1_4_TA0_3_B") (class "Default")
      (node (ref "CONN1") (pin "23") (pinfunction "23_23") (pintype "passive"))
      (node (ref "JP7") (pin "27") (pinfunction "27_27") (pintype "passive"))
      (node (ref "U4") (pin "22") (pinfunction "P1.4/TA0.3_22") (pintype "bidirectional"))
    )
    (net (code "16") (name "/P1_4_TA0_3_BUS") (class "Default")
      (node (ref "CONN2") (pin "23") (pinfunction "23_23") (pintype "passive"))
      (node (ref "CONN3") (pin "23") (pinfunction "23_23") (pintype "passive"))
      (node (ref "JP7") (pin "28") (pinfunction "28_28") (pintype "passive"))
      (node (ref "U$2") (pin "P$19") (pinfunction "P$19_P$19") (pintype "bidirectional"))
      (node (ref "U$4") (pin "P$19") (pinfunction "P$19_P$19") (pintype "bidirectional"))
      (node (ref "U$5") (pin "P$19") (pinfunction "P$19_P$19") (pintype "bidirectional"))
      (node (ref "U$6") (pin "P$19") (pinfunction "P$19_P$19") (pintype "bidirectional"))
      (node (ref "U$7") (pin "P$19") (pinfunction "P$19_P$19") (pintype "bidirectional"))
      (node (ref "U$8") (pin "P$19") (pinfunction "P$19_P$19") (pintype "bidirectional"))
    )
    (net (code "17") (name "/P1_5_TA0_4_B") (class "Default")
      (node (ref "CONN1") (pin "21") (pinfunction "21_21") (pintype "passive"))
      (node (ref "JP7") (pin "29") (pinfunction "29_29") (pintype "passive"))
      (node (ref "U4") (pin "23") (pinfunction "P1.5/TA0.4_23") (pintype "bidirectional"))
    )
    (net (code "18") (name "/P1_5_TA0_4_BUS") (class "Default")
      (node (ref "CONN2") (pin "21") (pinfunction "21_21") (pintype "passive"))
      (node (ref "CONN3") (pin "21") (pinfunction "21_21") (pintype "passive"))
      (node (ref "JP7") (pin "30") (pinfunction "30_30") (pintype "passive"))
      (node (ref "U$2") (pin "P$20") (pinfunction "P$20_P$20") (pintype "bidirectional"))
      (node (ref "U$4") (pin "P$20") (pinfunction "P$20_P$20") (pintype "bidirectional"))
      (node (ref "U$5") (pin "P$20") (pinfunction "P$20_P$20") (pintype "bidirectional"))
      (node (ref "U$6") (pin "P$20") (pinfunction "P$20_P$20") (pintype "bidirectional"))
      (node (ref "U$7") (pin "P$20") (pinfunction "P$20_P$20") (pintype "bidirectional"))
      (node (ref "U$8") (pin "P$20") (pinfunction "P$20_P$20") (pintype "bidirectional"))
    )
    (net (code "19") (name "/P1_7_RADIO_EN_B") (class "Default")
      (node (ref "JP2") (pin "10") (pinfunction "10_10") (pintype "passive"))
      (node (ref "U4") (pin "25") (pinfunction "P1.7/TA1.0_25") (pintype "bidirectional"))
    )
    (net (code "20") (name "/P2_1_RADIO_CS_B") (class "Default")
      (node (ref "JP2") (pin "8") (pinfunction "8_8") (pintype "passive"))
      (node (ref "U4") (pin "27") (pinfunction "P2.1/TA1.2_27") (pintype "bidirectional"))
    )
    (net (code "21") (name "/P2_3_RADIO_GDO0_B") (class "Default")
      (node (ref "JP2") (pin "14") (pinfunction "14_14") (pintype "passive"))
      (node (ref "U4") (pin "29") (pinfunction "P2.3/TA2.0_29") (pintype "bidirectional"))
    )
    (net (code "22") (name "/P2_4_RADIO_GDO2_B") (class "Default")
      (node (ref "JP2") (pin "6") (pinfunction "6_6") (pintype "passive"))
      (node (ref "U4") (pin "30") (pinfunction "P2.4/TA2.1_30") (pintype "bidirectional"))
    )
    (net (code "23") (name "/P2_7_UCA0_CLK_B") (class "Default")
      (node (ref "CONN1") (pin "26") (pinfunction "26_26") (pintype "passive"))
      (node (ref "JP7") (pin "19") (pinfunction "19_19") (pintype "passive"))
      (node (ref "U4") (pin "33") (pinfunction "P2.7/UCB0STE/UCA0CLK_33") (pintype "bidirectional"))
    )
    (net (code "24") (name "/P2_7_UCA0_CLK_BUS") (class "Default")
      (node (ref "CONN2") (pin "26") (pinfunction "26_26") (pintype "passive"))
      (node (ref "CONN3") (pin "26") (pinfunction "26_26") (pintype "passive"))
      (node (ref "JP7") (pin "20") (pinfunction "20_20") (pintype "passive"))
      (node (ref "U$2") (pin "P$13") (pinfunction "P$13_P$13") (pintype "bidirectional"))
      (node (ref "U$4") (pin "P$13") (pinfunction "P$13_P$13") (pintype "bidirectional"))
      (node (ref "U$5") (pin "P$13") (pinfunction "P$13_P$13") (pintype "bidirectional"))
      (node (ref "U$6") (pin "P$13") (pinfunction "P$13_P$13") (pintype "bidirectional"))
      (node (ref "U$7") (pin "P$13") (pinfunction "P$13_P$13") (pintype "bidirectional"))
      (node (ref "U$8") (pin "P$13") (pinfunction "P$13_P$13") (pintype "bidirectional"))
    )
    (net (code "25") (name "/P3_0_RADIO_MOSI_B") (class "Default")
      (node (ref "JP2") (pin "4") (pinfunction "4_4") (pintype "passive"))
      (node (ref "U4") (pin "34") (pinfunction "P3.0/UCB0SIMO/UCB0SDA_34") (pintype "bidirectional"))
    )
    (net (code "26") (name "/P3_1_RADIO_MISO_B") (class "Default")
      (node (ref "JP2") (pin "2") (pinfunction "2_2") (pintype "passive"))
      (node (ref "U4") (pin "35") (pinfunction "P3.1/UCB0SOMI/UCB0SCL_35") (pintype "bidirectional"))
    )
    (net (code "27") (name "/P3_2_RADIO_CLK_B") (class "Default")
      (node (ref "JP2") (pin "12") (pinfunction "12_12") (pintype "passive"))
      (node (ref "U4") (pin "36") (pinfunction "P3.2/UCB0CLK/UCA0STE_36") (pintype "bidirectional"))
    )
    (net (code "28") (name "/P3_3_UCA0_MOSI_B") (class "Default")
      (node (ref "CONN1") (pin "24") (pinfunction "24_24") (pintype "passive"))
      (node (ref "JP7") (pin "17") (pinfunction "17_17") (pintype "passive"))
      (node (ref "U4") (pin "37") (pinfunction "P3.3/UCA0TXD/UCA0SIMO_37") (pintype "bidirectional"))
    )
    (net (code "29") (name "/P3_3_UCA0_MOSI_BUS") (class "Default")
      (node (ref "CONN2") (pin "24") (pinfunction "24_24") (pintype "passive"))
      (node (ref "CONN3") (pin "24") (pinfunction "24_24") (pintype "passive"))
      (node (ref "JP7") (pin "18") (pinfunction "18_18") (pintype "passive"))
      (node (ref "U$2") (pin "P$12") (pinfunction "P$12_P$12") (pintype "bidirectional"))
      (node (ref "U$4") (pin "P$12") (pinfunction "P$12_P$12") (pintype "bidirectional"))
      (node (ref "U$5") (pin "P$12") (pinfunction "P$12_P$12") (pintype "bidirectional"))
      (node (ref "U$6") (pin "P$12") (pinfunction "P$12_P$12") (pintype "bidirectional"))
      (node (ref "U$7") (pin "P$12") (pinfunction "P$12_P$12") (pintype "bidirectional"))
      (node (ref "U$8") (pin "P$12") (pinfunction "P$12_P$12") (pintype "bidirectional"))
    )
    (net (code "30") (name "/P3_3_UCA0_TXD_EZFET") (class "Default")
      (node (ref "JP6") (pin "2") (pinfunction "2_2") (pintype "passive"))
      (node (ref "R20") (pin "2") (pinfunction "2_2") (pintype "passive"))
      (node (ref "U3") (pin "37") (pinfunction "37_37") (pintype "bidirectional"))
    )
    (net (code "31") (name "/P3_4_UCA0_MISO_B") (class "Default")
      (node (ref "CONN1") (pin "22") (pinfunction "22_22") (pintype "passive"))
      (node (ref "JP7") (pin "15") (pinfunction "15_15") (pintype "passive"))
      (node (ref "U4") (pin "38") (pinfunction "P3.4/UCA0RXD/UCA0SOMI_38") (pintype "bidirectional"))
    )
    (net (code "32") (name "/P3_4_UCA0_MISO_BUS") (class "Default")
      (node (ref "CONN2") (pin "22") (pinfunction "22_22") (pintype "passive"))
      (node (ref "CONN3") (pin "22") (pinfunction "22_22") (pintype "passive"))
      (node (ref "JP7") (pin "16") (pinfunction "16_16") (pintype "passive"))
      (node (ref "U$2") (pin "P$11") (pinfunction "P$11_P$11") (pintype "bidirectional"))
      (node (ref "U$4") (pin "P$11") (pinfunction "P$11_P$11") (pintype "bidirectional"))
      (node (ref "U$5") (pin "P$11") (pinfunction "P$11_P$11") (pintype "bidirectional"))
      (node (ref "U$6") (pin "P$11") (pinfunction "P$11_P$11") (pintype "bidirectional"))
      (node (ref "U$7") (pin "P$11") (pinfunction "P$11_P$11") (pintype "bidirectional"))
      (node (ref "U$8") (pin "P$11") (pinfunction "P$11_P$11") (pintype "bidirectional"))
    )
    (net (code "33") (name "/P3_4_UCA0_RXD_EZFET") (class "Default")
      (node (ref "JP6") (pin "1") (pinfunction "1_1") (pintype "passive"))
      (node (ref "R19") (pin "2") (pinfunction "2_2") (pintype "passive"))
      (node (ref "U3") (pin "38") (pinfunction "38_38") (pintype "bidirectional"))
    )
    (net (code "34") (name "/P4.6_B") (class "Default")
      (node (ref "CONN1") (pin "6") (pinfunction "6_6") (pintype "passive"))
      (node (ref "JP7") (pin "1") (pinfunction "1_1") (pintype "passive"))
      (node (ref "U4") (pin "47") (pinfunction "P4.6/PM_NONE_47") (pintype "bidirectional"))
    )
    (net (code "35") (name "/P4.7_B") (class "Default")
      (node (ref "CONN1") (pin "8") (pinfunction "8_8") (pintype "passive"))
      (node (ref "JP7") (pin "3") (pinfunction "3_3") (pintype "passive"))
      (node (ref "U4") (pin "48") (pinfunction "P4.7/PM_NONE_48") (pintype "bidirectional"))
    )
    (net (code "36") (name "/P4_0_B") (class "Default")
      (node (ref "CONN1") (pin "12") (pinfunction "12_12") (pintype "passive"))
      (node (ref "JP7") (pin "5") (pinfunction "5_5") (pintype "passive"))
      (node (ref "U4") (pin "41") (pinfunction "P4.0/PM_UCB1STE/PM_UCA1CLK_41") (pintype "bidirectional"))
    )
    (net (code "37") (name "/P4_0_BUS") (class "Default")
      (node (ref "CONN2") (pin "12") (pinfunction "12_12") (pintype "passive"))
      (node (ref "CONN3") (pin "12") (pinfunction "12_12") (pintype "passive"))
      (node (ref "JP7") (pin "6") (pinfunction "6_6") (pintype "passive"))
      (node (ref "U$2") (pin "P$6") (pinfunction "P$6_P$6") (pintype "bidirectional"))
      (node (ref "U$4") (pin "P$6") (pinfunction "P$6_P$6") (pintype "bidirectional"))
      (node (ref "U$5") (pin "P$6") (pinfunction "P$6_P$6") (pintype "bidirectional"))
      (node (ref "U$6") (pin "P$6") (pinfunction "P$6_P$6") (pintype "bidirectional"))
      (node (ref "U$7") (pin "P$6") (pinfunction "P$6_P$6") (pintype "bidirectional"))
      (node (ref "U$8") (pin "P$6") (pinfunction "P$6_P$6") (pintype "bidirectional"))
    )
    (net (code "38") (name "/P4_1_UCB1_I2C_SDA_B") (class "Default")
      (node (ref "CONN1") (pin "20") (pinfunction "20_20") (pintype "passive"))
      (node (ref "JP7") (pin "13") (pinfunction "13_13") (pintype "passive"))
      (node (ref "SW2") (pin "P$7") (pinfunction "COM2_P$7") (pintype "bidirectional"))
      (node (ref "U4") (pin "42") (pinfunction "P4.1/PM_UCB1SIMO/PM_UCB1SDA_42") (pintype "bidirectional"))
    )
    (net (code "39") (name "/P4_1_UCB1_I2C_SDA_BUS") (class "Default")
      (node (ref "CONN2") (pin "20") (pinfunction "20_20") (pintype "passive"))
      (node (ref "CONN3") (pin "20") (pinfunction "20_20") (pintype "passive"))
      (node (ref "JP4") (pin "2") (pinfunction "2_2") (pintype "passive"))
      (node (ref "JP7") (pin "14") (pinfunction "14_14") (pintype "passive"))
      (node (ref "SW1") (pin "P$5") (pinfunction "D_P$5") (pintype "bidirectional"))
      (node (ref "SW2") (pin "P$5") (pinfunction "D_P$5") (pintype "bidirectional"))
      (node (ref "U$2") (pin "P$10") (pinfunction "P$10_P$10") (pintype "bidirectional"))
      (node (ref "U$4") (pin "P$10") (pinfunction "P$10_P$10") (pintype "bidirectional"))
      (node (ref "U$5") (pin "P$10") (pinfunction "P$10_P$10") (pintype "bidirectional"))
      (node (ref "U$6") (pin "P$10") (pinfunction "P$10_P$10") (pintype "bidirectional"))
      (node (ref "U$7") (pin "P$10") (pinfunction "P$10_P$10") (pintype "bidirectional"))
      (node (ref "U$8") (pin "P$10") (pinfunction "P$10_P$10") (pintype "bidirectional"))
    )
    (net (code "40") (name "/P4_2_UCB1_I2C_SCL_B") (class "Default")
      (node (ref "CONN1") (pin "18") (pinfunction "18_18") (pintype "passive"))
      (node (ref "JP7") (pin "11") (pinfunction "11_11") (pintype "passive"))
      (node (ref "SW2") (pin "P$3") (pinfunction "COM1_P$3") (pintype "bidirectional"))
    )
    (net (code "41") (name "/P4_2_UCB1_I2C_SCL_BUS") (class "Default")
      (node (ref "CONN2") (pin "18") (pinfunction "18_18") (pintype "passive"))
      (node (ref "CONN3") (pin "18") (pinfunction "18_18") (pintype "passive"))
      (node (ref "JP4") (pin "4") (pinfunction "4_4") (pintype "passive"))
      (node (ref "JP7") (pin "12") (pinfunction "12_12") (pintype "passive"))
      (node (ref "SW1") (pin "P$1") (pinfunction "A_P$1") (pintype "bidirectional"))
      (node (ref "SW2") (pin "P$1") (pinfunction "A_P$1") (pintype "bidirectional"))
      (node (ref "U$2") (pin "P$9") (pinfunction "P$9_P$9") (pintype "bidirectional"))
      (node (ref "U$4") (pin "P$9") (pinfunction "P$9_P$9") (pintype "bidirectional"))
      (node (ref "U$5") (pin "P$9") (pinfunction "P$9_P$9") (pintype "bidirectional"))
      (node (ref "U$6") (pin "P$9") (pinfunction "P$9_P$9") (pintype "bidirectional"))
      (node (ref "U$7") (pin "P$9") (pinfunction "P$9_P$9") (pintype "bidirectional"))
      (node (ref "U$8") (pin "P$9") (pinfunction "P$9_P$9") (pintype "bidirectional"))
      (node (ref "U4") (pin "43") (pinfunction "P4.2/PM_UCB1SOMI/PM_UCB1SCL_43") (pintype "bidirectional"))
    )
    (net (code "42") (name "/P4_4_UCA1_TXD_B") (class "Default")
      (node (ref "CONN1") (pin "14") (pinfunction "14_14") (pintype "passive"))
      (node (ref "JP7") (pin "7") (pinfunction "7_7") (pintype "passive"))
      (node (ref "SW4") (pin "P$6") (pinfunction "E_P$6") (pintype "bidirectional"))
      (node (ref "U4") (pin "45") (pinfunction "P4.4/PM_UCA1TXD/PM_UCA1SIMO_45") (pintype "bidirectional"))
    )
    (net (code "43") (name "/P4_4_UCA1_TXD_BUS") (class "Default")
      (node (ref "CONN2") (pin "14") (pinfunction "14_14") (pintype "passive"))
      (node (ref "CONN3") (pin "14") (pinfunction "14_14") (pintype "passive"))
      (node (ref "JP7") (pin "8") (pinfunction "8_8") (pintype "passive"))
      (node (ref "SW4") (pin "P$5") (pinfunction "D_P$5") (pintype "bidirectional"))
      (node (ref "U$2") (pin "P$7") (pinfunction "P$7_P$7") (pintype "bidirectional"))
      (node (ref "U$4") (pin "P$7") (pinfunction "P$7_P$7") (pintype "bidirectional"))
      (node (ref "U$5") (pin "P$7") (pinfunction "P$7_P$7") (pintype "bidirectional"))
      (node (ref "U$6") (pin "P$7") (pinfunction "P$7_P$7") (pintype "bidirectional"))
      (node (ref "U$7") (pin "P$7") (pinfunction "P$7_P$7") (pintype "bidirectional"))
      (node (ref "U$8") (pin "P$7") (pinfunction "P$7_P$7") (pintype "bidirectional"))
    )
    (net (code "44") (name "/P4_5_UCA1_RXD_B") (class "Default")
      (node (ref "CONN1") (pin "16") (pinfunction "16_16") (pintype "passive"))
      (node (ref "JP7") (pin "9") (pinfunction "9_9") (pintype "passive"))
      (node (ref "SW4") (pin "P$2") (pinfunction "B_P$2") (pintype "bidirectional"))
      (node (ref "U4") (pin "46") (pinfunction "P4.5/PM_UCA1RXD/PM_UCA1SOMI_46") (pintype "bidirectional"))
    )
    (net (code "45") (name "/P4_5_UCA1_RXD_BUS") (class "Default")
      (node (ref "CONN2") (pin "16") (pinfunction "16_16") (pintype "passive"))
      (node (ref "CONN3") (pin "16") (pinfunction "16_16") (pintype "passive"))
      (node (ref "JP7") (pin "10") (pinfunction "10_10") (pintype "passive"))
      (node (ref "SW4") (pin "P$1") (pinfunction "A_P$1") (pintype "bidirectional"))
      (node (ref "U$2") (pin "P$8") (pinfunction "P$8_P$8") (pintype "bidirectional"))
      (node (ref "U$4") (pin "P$8") (pinfunction "P$8_P$8") (pintype "bidirectional"))
      (node (ref "U$5") (pin "P$8") (pinfunction "P$8_P$8") (pintype "bidirectional"))
      (node (ref "U$6") (pin "P$8") (pinfunction "P$8_P$8") (pintype "bidirectional"))
      (node (ref "U$7") (pin "P$8") (pinfunction "P$8_P$8") (pintype "bidirectional"))
      (node (ref "U$8") (pin "P$8") (pinfunction "P$8_P$8") (pintype "bidirectional"))
    )
    (net (code "46") (name "/P4_6_BUS") (class "Default")
      (node (ref "CONN2") (pin "6") (pinfunction "6_6") (pintype "passive"))
      (node (ref "CONN3") (pin "6") (pinfunction "6_6") (pintype "passive"))
      (node (ref "JP7") (pin "2") (pinfunction "2_2") (pintype "passive"))
      (node (ref "U$2") (pin "P$3") (pinfunction "P$3_P$3") (pintype "bidirectional"))
      (node (ref "U$4") (pin "P$3") (pinfunction "P$3_P$3") (pintype "bidirectional"))
      (node (ref "U$5") (pin "P$3") (pinfunction "P$3_P$3") (pintype "bidirectional"))
      (node (ref "U$6") (pin "P$3") (pinfunction "P$3_P$3") (pintype "bidirectional"))
      (node (ref "U$7") (pin "P$3") (pinfunction "P$3_P$3") (pintype "bidirectional"))
      (node (ref "U$8") (pin "P$3") (pinfunction "P$3_P$3") (pintype "bidirectional"))
    )
    (net (code "47") (name "/P4_7_BUS") (class "Default")
      (node (ref "CONN2") (pin "8") (pinfunction "8_8") (pintype "passive"))
      (node (ref "CONN3") (pin "8") (pinfunction "8_8") (pintype "passive"))
      (node (ref "JP7") (pin "4") (pinfunction "4_4") (pintype "passive"))
      (node (ref "U$2") (pin "P$4") (pinfunction "P$4_P$4") (pintype "bidirectional"))
      (node (ref "U$4") (pin "P$4") (pinfunction "P$4_P$4") (pintype "bidirectional"))
      (node (ref "U$5") (pin "P$4") (pinfunction "P$4_P$4") (pintype "bidirectional"))
      (node (ref "U$6") (pin "P$4") (pinfunction "P$4_P$4") (pintype "bidirectional"))
      (node (ref "U$7") (pin "P$4") (pinfunction "P$4_P$4") (pintype "bidirectional"))
      (node (ref "U$8") (pin "P$4") (pinfunction "P$4_P$4") (pintype "bidirectional"))
    )
    (net (code "48") (name "/P5_2_B") (class "Default")
      (node (ref "CONN1") (pin "7") (pinfunction "7_7") (pintype "passive"))
      (node (ref "JP7") (pin "33") (pinfunction "33_33") (pintype "passive"))
      (node (ref "U4") (pin "57") (pinfunction "P5.2/XT2IN_57") (pintype "bidirectional"))
    )
    (net (code "49") (name "/P5_2_BUS") (class "Default")
      (node (ref "CONN2") (pin "7") (pinfunction "7_7") (pintype "passive"))
      (node (ref "CONN3") (pin "7") (pinfunction "7_7") (pintype "passive"))
      (node (ref "JP7") (pin "34") (pinfunction "34_34") (pintype "passive"))
      (node (ref "U$2") (pin "P$27") (pinfunction "P$27_P$27") (pintype "bidirectional"))
      (node (ref "U$4") (pin "P$27") (pinfunction "P$27_P$27") (pintype "bidirectional"))
      (node (ref "U$5") (pin "P$27") (pinfunction "P$27_P$27") (pintype "bidirectional"))
      (node (ref "U$6") (pin "P$27") (pinfunction "P$27_P$27") (pintype "bidirectional"))
      (node (ref "U$7") (pin "P$27") (pinfunction "P$27_P$27") (pintype "bidirectional"))
      (node (ref "U$8") (pin "P$27") (pinfunction "P$27_P$27") (pintype "bidirectional"))
    )
    (net (code "50") (name "/P5_3_B") (class "Default")
      (node (ref "CONN1") (pin "17") (pinfunction "17_17") (pintype "passive"))
      (node (ref "JP7") (pin "31") (pinfunction "31_31") (pintype "passive"))
      (node (ref "U4") (pin "58") (pinfunction "P5.3/XT2OUT_58") (pintype "bidirectional"))
    )
    (net (code "51") (name "/P5_3_BUS") (class "Default")
      (node (ref "CONN2") (pin "17") (pinfunction "17_17") (pintype "passive"))
      (node (ref "CONN3") (pin "17") (pinfunction "17_17") (pintype "passive"))
      (node (ref "JP7") (pin "32") (pinfunction "32_32") (pintype "passive"))
      (node (ref "U$2") (pin "P$22") (pinfunction "P$22_P$22") (pintype "bidirectional"))
      (node (ref "U$4") (pin "P$22") (pinfunction "P$22_P$22") (pintype "bidirectional"))
      (node (ref "U$5") (pin "P$22") (pinfunction "P$22_P$22") (pintype "bidirectional"))
      (node (ref "U$6") (pin "P$22") (pinfunction "P$22_P$22") (pintype "bidirectional"))
      (node (ref "U$7") (pin "P$22") (pinfunction "P$22_P$22") (pintype "bidirectional"))
      (node (ref "U$8") (pin "P$22") (pinfunction "P$22_P$22") (pintype "bidirectional"))
    )
    (net (code "52") (name "/P6_0_AIN_0_B") (class "Default")
      (node (ref "CONN1") (pin "1") (pinfunction "1_1") (pintype "passive"))
      (node (ref "JP7") (pin "39") (pinfunction "39_39") (pintype "passive"))
      (node (ref "U4") (pin "1") (pinfunction "P6.0/CB0/A0_1") (pintype "bidirectional"))
    )
    (net (code "53") (name "/P6_0_AIN_0_BUS") (class "Default")
      (node (ref "CONN2") (pin "1") (pinfunction "1_1") (pintype "passive"))
      (node (ref "CONN3") (pin "1") (pinfunction "1_1") (pintype "passive"))
      (node (ref "JP7") (pin "40") (pinfunction "40_40") (pintype "passive"))
      (node (ref "U$2") (pin "P$30") (pinfunction "P$30_P$30") (pintype "bidirectional"))
      (node (ref "U$4") (pin "P$30") (pinfunction "P$30_P$30") (pintype "bidirectional"))
      (node (ref "U$5") (pin "P$30") (pinfunction "P$30_P$30") (pintype "bidirectional"))
      (node (ref "U$6") (pin "P$30") (pinfunction "P$30_P$30") (pintype "bidirectional"))
      (node (ref "U$7") (pin "P$30") (pinfunction "P$30_P$30") (pintype "bidirectional"))
      (node (ref "U$8") (pin "P$30") (pinfunction "P$30_P$30") (pintype "bidirectional"))
    )
    (net (code "54") (name "/P6_2_AIN_2_B") (class "Default")
      (node (ref "CONN1") (pin "5") (pinfunction "5_5") (pintype "passive"))
      (node (ref "JP7") (pin "35") (pinfunction "35_35") (pintype "passive"))
      (node (ref "U4") (pin "3") (pinfunction "P6.2/CB2/A2_3") (pintype "bidirectional"))
    )
    (net (code "55") (name "/P6_2_AIN_2_BUS") (class "Default")
      (node (ref "CONN2") (pin "5") (pinfunction "5_5") (pintype "passive"))
      (node (ref "CONN3") (pin "5") (pinfunction "5_5") (pintype "passive"))
      (node (ref "JP7") (pin "36") (pinfunction "36_36") (pintype "passive"))
      (node (ref "U$2") (pin "P$28") (pinfunction "P$28_P$28") (pintype "bidirectional"))
      (node (ref "U$4") (pin "P$28") (pinfunction "P$28_P$28") (pintype "bidirectional"))
      (node (ref "U$5") (pin "P$28") (pinfunction "P$28_P$28") (pintype "bidirectional"))
      (node (ref "U$6") (pin "P$28") (pinfunction "P$28_P$28") (pintype "bidirectional"))
      (node (ref "U$7") (pin "P$28") (pinfunction "P$28_P$28") (pintype "bidirectional"))
      (node (ref "U$8") (pin "P$28") (pinfunction "P$28_P$28") (pintype "bidirectional"))
    )
    (net (code "56") (name "/P6_6_AIN_6_B") (class "Default")
      (node (ref "CONN1") (pin "3") (pinfunction "3_3") (pintype "passive"))
      (node (ref "JP7") (pin "37") (pinfunction "37_37") (pintype "passive"))
      (node (ref "U4") (pin "7") (pinfunction "P6.6/CB6/A6_7") (pintype "bidirectional"))
    )
    (net (code "57") (name "/P6_6_AIN_6_BUS") (class "Default")
      (node (ref "CONN2") (pin "3") (pinfunction "3_3") (pintype "passive"))
      (node (ref "CONN3") (pin "3") (pinfunction "3_3") (pintype "passive"))
      (node (ref "JP7") (pin "38") (pinfunction "38_38") (pintype "passive"))
      (node (ref "U$2") (pin "P$29") (pinfunction "P$29_P$29") (pintype "bidirectional"))
      (node (ref "U$4") (pin "P$29") (pinfunction "P$29_P$29") (pintype "bidirectional"))
      (node (ref "U$5") (pin "P$29") (pinfunction "P$29_P$29") (pintype "bidirectional"))
      (node (ref "U$6") (pin "P$29") (pinfunction "P$29_P$29") (pintype "bidirectional"))
      (node (ref "U$7") (pin "P$29") (pinfunction "P$29_P$29") (pintype "bidirectional"))
      (node (ref "U$8") (pin "P$29") (pinfunction "P$29_P$29") (pintype "bidirectional"))
    )
    (net (code "58") (name "/POWER_BOARD_VDD") (class "Default")
      (node (ref "JP3") (pin "2") (pinfunction "2_2") (pintype "passive"))
      (node (ref "U$9") (pin "P$1") (pinfunction "P$1_P$1") (pintype "bidirectional"))
      (node (ref "U$9") (pin "P$16") (pinfunction "P$16_P$16") (pintype "bidirectional"))
    )
    (net (code "59") (name "/RADIO_CLK") (class "Default")
      (node (ref "JP2") (pin "11") (pinfunction "11_11") (pintype "passive"))
      (node (ref "JP8") (pin "11") (pinfunction "11_11") (pintype "passive"))
      (node (ref "RADIO_CONN") (pin "P$1") (pinfunction "P$1_P$1") (pintype "bidirectional"))
    )
    (net (code "60") (name "/RADIO_CS") (class "Default")
      (node (ref "JP2") (pin "7") (pinfunction "7_7") (pintype "passive"))
      (node (ref "JP8") (pin "7") (pinfunction "7_7") (pintype "passive"))
      (node (ref "RADIO_CONN") (pin "P$7") (pinfunction "P$7_P$7") (pintype "bidirectional"))
    )
    (net (code "61") (name "/RADIO_EN") (class "Default")
      (node (ref "JP2") (pin "9") (pinfunction "9_9") (pintype "passive"))
      (node (ref "JP8") (pin "9") (pinfunction "9_9") (pintype "passive"))
      (node (ref "RADIO_CONN") (pin "P$6") (pinfunction "P$6_P$6") (pintype "bidirectional"))
    )
    (net (code "62") (name "/RADIO_GDO0") (class "Default")
      (node (ref "JP2") (pin "13") (pinfunction "13_13") (pintype "passive"))
      (node (ref "JP8") (pin "13") (pinfunction "13_13") (pintype "passive"))
      (node (ref "RADIO_CONN") (pin "P$2") (pinfunction "P$2_P$2") (pintype "bidirectional"))
    )
    (net (code "63") (name "/RADIO_GDO2") (class "Default")
      (node (ref "JP2") (pin "5") (pinfunction "5_5") (pintype "passive"))
      (node (ref "JP8") (pin "5") (pinfunction "5_5") (pintype "passive"))
      (node (ref "RADIO_CONN") (pin "P$8") (pinfunction "P$8_P$8") (pintype "bidirectional"))
    )
    (net (code "64") (name "/RADIO_MISO") (class "Default")
      (node (ref "JP2") (pin "1") (pinfunction "1_1") (pintype "passive"))
      (node (ref "JP8") (pin "1") (pinfunction "1_1") (pintype "passive"))
      (node (ref "RADIO_CONN") (pin "P$10") (pinfunction "P$10_P$10") (pintype "bidirectional"))
    )
    (net (code "65") (name "/RADIO_MOSI") (class "Default")
      (node (ref "JP2") (pin "3") (pinfunction "3_3") (pintype "passive"))
      (node (ref "JP8") (pin "3") (pinfunction "3_3") (pintype "passive"))
      (node (ref "RADIO_CONN") (pin "P$9") (pinfunction "P$9_P$9") (pintype "bidirectional"))
    )
    (net (code "66") (name "/SCL_PWR_BOARD") (class "Default")
      (node (ref "SW1") (pin "P$3") (pinfunction "COM1_P$3") (pintype "bidirectional"))
      (node (ref "U$9") (pin "P$9") (pinfunction "P$9_P$9") (pintype "bidirectional"))
    )
    (net (code "67") (name "/SDA_PWR_BOARD") (class "Default")
      (node (ref "SW1") (pin "P$7") (pinfunction "COM2_P$7") (pintype "bidirectional"))
      (node (ref "U$9") (pin "P$10") (pinfunction "P$10_P$10") (pintype "bidirectional"))
    )
    (net (code "68") (name "/SHIELD") (class "Default")
      (node (ref "EZUSB") (pin "M1") (pinfunction "GND1_M1") (pintype "bidirectional"))
      (node (ref "EZUSB") (pin "M2") (pinfunction "GND2_M2") (pintype "bidirectional"))
      (node (ref "EZUSB") (pin "M3") (pinfunction "GND3_M3") (pintype "bidirectional"))
      (node (ref "EZUSB") (pin "M4") (pinfunction "GND4_M4") (pintype "bidirectional"))
      (node (ref "R21") (pin "1") (pinfunction "1_1") (pintype "passive"))
      (node (ref "U2") (pin "5") (pinfunction "IO4_5") (pintype "bidirectional"))
    )
    (net (code "69") (name "/TCK") (class "Default")
      (node (ref "JP12") (pin "11") (pinfunction "11_11") (pintype "passive"))
      (node (ref "JP14") (pin "11") (pinfunction "11_11") (pintype "passive"))
      (node (ref "JP5") (pin "12") (pinfunction "12_12") (pintype "passive"))
      (node (ref "TI_JTAG") (pin "7") (pinfunction "7_7") (pintype "passive"))
    )
    (net (code "70") (name "/TCK_B") (class "Default")
      (node (ref "CONN1") (pin "15") (pinfunction "15_15") (pintype "passive"))
      (node (ref "JP12") (pin "12") (pinfunction "12_12") (pintype "passive"))
      (node (ref "U4") (pin "63") (pinfunction "PJ.3/TCK_63") (pintype "bidirectional"))
    )
    (net (code "71") (name "/TCK_BUS") (class "Default")
      (node (ref "CONN2") (pin "15") (pinfunction "15_15") (pintype "passive"))
      (node (ref "CONN3") (pin "15") (pinfunction "15_15") (pintype "passive"))
      (node (ref "JP14") (pin "12") (pinfunction "12_12") (pintype "passive"))
      (node (ref "U$10") (pin "P$5") (pinfunction "P$5_P$5") (pintype "bidirectional"))
      (node (ref "U$2") (pin "P$23") (pinfunction "P$23_P$23") (pintype "bidirectional"))
      (node (ref "U$4") (pin "P$23") (pinfunction "P$23_P$23") (pintype "bidirectional"))
      (node (ref "U$5") (pin "P$23") (pinfunction "P$23_P$23") (pintype "bidirectional"))
      (node (ref "U$6") (pin "P$23") (pinfunction "P$23_P$23") (pintype "bidirectional"))
      (node (ref "U$7") (pin "P$23") (pinfunction "P$23_P$23") (pintype "bidirectional"))
      (node (ref "U$8") (pin "P$23") (pinfunction "P$23_P$23") (pintype "bidirectional"))
    )
    (net (code "72") (name "/TCK_EZFET") (class "Default")
      (node (ref "JP5") (pin "11") (pinfunction "11_11") (pintype "passive"))
      (node (ref "U3") (pin "63") (pinfunction "63_63") (pintype "bidirectional"))
    )
    (net (code "73") (name "/TDI") (class "Default")
      (node (ref "JP12") (pin "7") (pinfunction "7_7") (pintype "passive"))
      (node (ref "JP14") (pin "7") (pinfunction "7_7") (pintype "passive"))
      (node (ref "JP5") (pin "8") (pinfunction "8_8") (pintype "passive"))
      (node (ref "TI_JTAG") (pin "3") (pinfunction "3_3") (pintype "passive"))
    )
    (net (code "74") (name "/TDI_B") (class "Default")
      (node (ref "CONN1") (pin "13") (pinfunction "13_13") (pintype "passive"))
      (node (ref "JP12") (pin "8") (pinfunction "8_8") (pintype "passive"))
      (node (ref "U4") (pin "61") (pinfunction "PJ.1/TDI/TCLK_61") (pintype "bidirectional"))
    )
    (net (code "75") (name "/TDI_BUS") (class "Default")
      (node (ref "CONN2") (pin "13") (pinfunction "13_13") (pintype "passive"))
      (node (ref "CONN3") (pin "13") (pinfunction "13_13") (pintype "passive"))
      (node (ref "JP14") (pin "8") (pinfunction "8_8") (pintype "passive"))
      (node (ref "U$10") (pin "P$6") (pinfunction "P$6_P$6") (pintype "bidirectional"))
      (node (ref "U$2") (pin "P$24") (pinfunction "P$24_P$24") (pintype "bidirectional"))
      (node (ref "U$4") (pin "P$24") (pinfunction "P$24_P$24") (pintype "bidirectional"))
      (node (ref "U$5") (pin "P$24") (pinfunction "P$24_P$24") (pintype "bidirectional"))
      (node (ref "U$6") (pin "P$24") (pinfunction "P$24_P$24") (pintype "bidirectional"))
      (node (ref "U$7") (pin "P$24") (pinfunction "P$24_P$24") (pintype "bidirectional"))
      (node (ref "U$8") (pin "P$24") (pinfunction "P$24_P$24") (pintype "bidirectional"))
    )
    (net (code "76") (name "/TDI_EZFET") (class "Default")
      (node (ref "JP5") (pin "7") (pinfunction "7_7") (pintype "passive"))
      (node (ref "U3") (pin "61") (pinfunction "61_61") (pintype "bidirectional"))
    )
    (net (code "77") (name "/TDO") (class "Default")
      (node (ref "JP12") (pin "5") (pinfunction "5_5") (pintype "passive"))
      (node (ref "JP14") (pin "5") (pinfunction "5_5") (pintype "passive"))
      (node (ref "JP5") (pin "6") (pinfunction "6_6") (pintype "passive"))
      (node (ref "TI_JTAG") (pin "1") (pinfunction "1_1") (pintype "passive"))
    )
    (net (code "78") (name "/TDO_B") (class "Default")
      (node (ref "CONN1") (pin "11") (pinfunction "11_11") (pintype "passive"))
      (node (ref "JP12") (pin "6") (pinfunction "6_6") (pintype "passive"))
      (node (ref "U4") (pin "60") (pinfunction "PJ.0/TDO_60") (pintype "bidirectional"))
    )
    (net (code "79") (name "/TDO_BUS") (class "Default")
      (node (ref "CONN2") (pin "11") (pinfunction "11_11") (pintype "passive"))
      (node (ref "CONN3") (pin "11") (pinfunction "11_11") (pintype "passive"))
      (node (ref "JP14") (pin "6") (pinfunction "6_6") (pintype "passive"))
      (node (ref "U$10") (pin "P$7") (pinfunction "P$7_P$7") (pintype "bidirectional"))
      (node (ref "U$2") (pin "P$25") (pinfunction "P$25_P$25") (pintype "bidirectional"))
      (node (ref "U$4") (pin "P$25") (pinfunction "P$25_P$25") (pintype "bidirectional"))
      (node (ref "U$5") (pin "P$25") (pinfunction "P$25_P$25") (pintype "bidirectional"))
      (node (ref "U$6") (pin "P$25") (pinfunction "P$25_P$25") (pintype "bidirectional"))
      (node (ref "U$7") (pin "P$25") (pinfunction "P$25_P$25") (pintype "bidirectional"))
      (node (ref "U$8") (pin "P$25") (pinfunction "P$25_P$25") (pintype "bidirectional"))
    )
    (net (code "80") (name "/TDO_EZFET") (class "Default")
      (node (ref "JP5") (pin "5") (pinfunction "5_5") (pintype "passive"))
      (node (ref "U3") (pin "60") (pinfunction "60_60") (pintype "bidirectional"))
    )
    (net (code "81") (name "/TEST") (class "Default")
      (node (ref "JP12") (pin "3") (pinfunction "3_3") (pintype "passive"))
      (node (ref "JP14") (pin "3") (pinfunction "3_3") (pintype "passive"))
      (node (ref "JP5") (pin "4") (pinfunction "4_4") (pintype "passive"))
      (node (ref "TI_JTAG") (pin "8") (pinfunction "8_8") (pintype "passive"))
    )
    (net (code "82") (name "/TEST_B") (class "Default")
      (node (ref "CONN1") (pin "10") (pinfunction "10_10") (pintype "passive"))
      (node (ref "JP12") (pin "4") (pinfunction "4_4") (pintype "passive"))
      (node (ref "SW3") (pin "P$1") (pinfunction "A_P$1") (pintype "bidirectional"))
      (node (ref "U4") (pin "59") (pinfunction "TEST/SBWTCK_59") (pintype "input"))
    )
    (net (code "83") (name "/TEST_BUS") (class "Default")
      (node (ref "CONN2") (pin "10") (pinfunction "10_10") (pintype "passive"))
      (node (ref "CONN3") (pin "10") (pinfunction "10_10") (pintype "passive"))
      (node (ref "JP14") (pin "4") (pinfunction "4_4") (pintype "passive"))
      (node (ref "SW3") (pin "P$2") (pinfunction "B_P$2") (pintype "bidirectional"))
      (node (ref "U$10") (pin "P$9") (pinfunction "P$9_P$9") (pintype "bidirectional"))
      (node (ref "U$2") (pin "P$5") (pinfunction "P$5_P$5") (pintype "bidirectional"))
      (node (ref "U$4") (pin "P$5") (pinfunction "P$5_P$5") (pintype "bidirectional"))
      (node (ref "U$5") (pin "P$5") (pinfunction "P$5_P$5") (pintype "bidirectional"))
      (node (ref "U$6") (pin "P$5") (pinfunction "P$5_P$5") (pintype "bidirectional"))
      (node (ref "U$7") (pin "P$5") (pinfunction "P$5_P$5") (pintype "bidirectional"))
      (node (ref "U$8") (pin "P$5") (pinfunction "P$5_P$5") (pintype "bidirectional"))
    )
    (net (code "84") (name "/TEST_EZFET") (class "Default")
      (node (ref "JP5") (pin "3") (pinfunction "3_3") (pintype "passive"))
      (node (ref "U3") (pin "59") (pinfunction "59_59") (pintype "input"))
    )
    (net (code "85") (name "/TMS") (class "Default")
      (node (ref "JP12") (pin "9") (pinfunction "9_9") (pintype "passive"))
      (node (ref "JP14") (pin "9") (pinfunction "9_9") (pintype "passive"))
      (node (ref "JP5") (pin "10") (pinfunction "10_10") (pintype "passive"))
      (node (ref "TI_JTAG") (pin "5") (pinfunction "5_5") (pintype "passive"))
    )
    (net (code "86") (name "/TMS_B") (class "Default")
      (node (ref "CONN1") (pin "9") (pinfunction "9_9") (pintype "passive"))
      (node (ref "JP12") (pin "10") (pinfunction "10_10") (pintype "passive"))
      (node (ref "U4") (pin "62") (pinfunction "PJ.2/TMS_62") (pintype "bidirectional"))
    )
    (net (code "87") (name "/TMS_BUS") (class "Default")
      (node (ref "CONN2") (pin "9") (pinfunction "9_9") (pintype "passive"))
      (node (ref "CONN3") (pin "9") (pinfunction "9_9") (pintype "passive"))
      (node (ref "JP14") (pin "10") (pinfunction "10_10") (pintype "passive"))
      (node (ref "U$10") (pin "P$8") (pinfunction "P$8_P$8") (pintype "bidirectional"))
      (node (ref "U$2") (pin "P$26") (pinfunction "P$26_P$26") (pintype "bidirectional"))
      (node (ref "U$4") (pin "P$26") (pinfunction "P$26_P$26") (pintype "bidirectional"))
      (node (ref "U$5") (pin "P$26") (pinfunction "P$26_P$26") (pintype "bidirectional"))
      (node (ref "U$6") (pin "P$26") (pinfunction "P$26_P$26") (pintype "bidirectional"))
      (node (ref "U$7") (pin "P$26") (pinfunction "P$26_P$26") (pintype "bidirectional"))
      (node (ref "U$8") (pin "P$26") (pinfunction "P$26_P$26") (pintype "bidirectional"))
    )
    (net (code "88") (name "/TMS_EZFET") (class "Default")
      (node (ref "JP5") (pin "9") (pinfunction "9_9") (pintype "passive"))
      (node (ref "U3") (pin "62") (pinfunction "62_62") (pintype "bidirectional"))
    )
    (net (code "89") (name "/T_NC_MSC_EZFET") (class "Default")
      (node (ref "JP16") (pin "1") (pinfunction "1_1") (pintype "passive"))
      (node (ref "U3") (pin "45") (pinfunction "45_45") (pintype "bidirectional"))
    )
    (net (code "90") (name "/T_RST_EZFET") (class "Default")
      (node (ref "JP16") (pin "4") (pinfunction "4_4") (pintype "passive"))
      (node (ref "R18") (pin "1") (pinfunction "1_1") (pintype "passive"))
      (node (ref "U3") (pin "43") (pinfunction "43_43") (pintype "bidirectional"))
    )
    (net (code "91") (name "/T_TEST_TCLK_EZFET") (class "Default")
      (node (ref "JP16") (pin "2") (pinfunction "2_2") (pintype "passive"))
      (node (ref "R15") (pin "2") (pinfunction "2_2") (pintype "passive"))
      (node (ref "U3") (pin "44") (pinfunction "44_44") (pintype "bidirectional"))
    )
    (net (code "92") (name "/USB_AVBUS") (class "Default")
      (node (ref "C6") (pin "1") (pinfunction "1_1") (pintype "passive"))
      (node (ref "R3") (pin "2") (pinfunction "2_2") (pintype "passive"))
      (node (ref "R4") (pin "2") (pinfunction "2_2") (pintype "passive"))
      (node (ref "U3") (pin "1") (pinfunction "1_1") (pintype "bidirectional"))
    )
    (net (code "93") (name "/USB_AVCC2ADC") (class "Default")
      (node (ref "C7") (pin "2") (pinfunction "2_2") (pintype "passive"))
      (node (ref "R5") (pin "2") (pinfunction "2_2") (pintype "passive"))
      (node (ref "R6") (pin "1") (pinfunction "1_1") (pintype "passive"))
      (node (ref "U3") (pin "2") (pinfunction "2_2") (pintype "bidirectional"))
    )
    (net (code "94") (name "/USB_D+") (class "Default")
      (node (ref "C14") (pin "1") (pinfunction "1_1") (pintype "passive"))
      (node (ref "R1") (pin "1") (pinfunction "1_1") (pintype "passive"))
      (node (ref "R7") (pin "1") (pinfunction "1_1") (pintype "passive"))
      (node (ref "R9") (pin "2") (pinfunction "2_2") (pintype "passive"))
      (node (ref "U3") (pin "50") (pinfunction "50_50") (pintype "bidirectional"))
    )
    (net (code "95") (name "/USB_D-") (class "Default")
      (node (ref "C13") (pin "1") (pinfunction "1_1") (pintype "passive"))
      (node (ref "R8") (pin "2") (pinfunction "2_2") (pintype "passive"))
      (node (ref "U3") (pin "52") (pinfunction "52_52") (pintype "bidirectional"))
    )
    (net (code "96") (name "/USB_PUR") (class "Default")
      (node (ref "R1") (pin "2") (pinfunction "2_2") (pintype "passive"))
      (node (ref "U3") (pin "51") (pinfunction "51_51") (pintype "bidirectional"))
    )
    (net (code "97") (name "/V18") (class "Default")
      (node (ref "U4") (pin "55") (pinfunction "V18_55") (pintype "power_in"))
    )
    (net (code "98") (name "/V18_EZFET") (class "Default")
      (node (ref "C15") (pin "1") (pinfunction "1_1") (pintype "passive"))
      (node (ref "U3") (pin "55") (pinfunction "55_55") (pintype "power_in"))
    )
    (net (code "99") (name "/VCC_EZFET") (class "Default")
      (node (ref "C10") (pin "2") (pinfunction "2_2") (pintype "passive"))
      (node (ref "C11") (pin "2") (pinfunction "2_2") (pintype "passive"))
      (node (ref "C12") (pin "2") (pinfunction "2_2") (pintype "passive"))
      (node (ref "C9") (pin "2") (pinfunction "2_2") (pintype "passive"))
      (node (ref "JP16") (pin "8") (pinfunction "8_8") (pintype "passive"))
      (node (ref "JP17") (pin "1") (pinfunction "1_1") (pintype "passive"))
      (node (ref "JP17") (pin "2") (pinfunction "2_2") (pintype "passive"))
      (node (ref "JP17") (pin "3") (pinfunction "3_3") (pintype "passive"))
      (node (ref "JP17") (pin "4") (pinfunction "4_4") (pintype "passive"))
      (node (ref "JP5") (pin "1") (pinfunction "1_1") (pintype "passive"))
      (node (ref "R14") (pin "2") (pinfunction "2_2") (pintype "passive"))
      (node (ref "R2") (pin "2") (pinfunction "2_2") (pintype "passive"))
      (node (ref "R22") (pin "1") (pinfunction "1_1") (pintype "passive"))
      (node (ref "R5") (pin "1") (pinfunction "1_1") (pintype "passive"))
      (node (ref "TP3") (pin "P$1") (pinfunction "P$1_P$1") (pintype "bidirectional"))
      (node (ref "U3") (pin "11") (pinfunction "11_11") (pintype "power_in"))
      (node (ref "U3") (pin "15") (pinfunction "15_15") (pintype "power_in"))
      (node (ref "U3") (pin "40") (pinfunction "40_40") (pintype "power_in"))
    )
    (net (code "100") (name "/VDD") (class "Default")
      (node (ref "C26") (pin "2") (pinfunction "2_2") (pintype "passive"))
      (node (ref "C27") (pin "2") (pinfunction "2_2") (pintype "passive"))
      (node (ref "C28") (pin "2") (pinfunction "2_2") (pintype "passive"))
      (node (ref "C29") (pin "2") (pinfunction "2_2") (pintype "passive"))
      (node (ref "C30") (pin "2") (pinfunction "2_2") (pintype "passive"))
      (node (ref "C31") (pin "2") (pinfunction "2_2") (pintype "passive"))
      (node (ref "C32") (pin "2") (pinfunction "2_2") (pintype "passive"))
      (node (ref "C33") (pin "2") (pinfunction "2_2") (pintype "passive"))
      (node (ref "CONN2") (pin "2") (pinfunction "2_2") (pintype "passive"))
      (node (ref "CONN2") (pin "29") (pinfunction "29_29") (pintype "passive"))
      (node (ref "CONN3") (pin "2") (pinfunction "2_2") (pintype "passive"))
      (node (ref "CONN3") (pin "29") (pinfunction "29_29") (pintype "passive"))
      (node (ref "JP1") (pin "5") (pinfunction "5_5") (pintype "passive"))
      (node (ref "JP14") (pin "2") (pinfunction "2_2") (pintype "passive"))
      (node (ref "JP15") (pin "1") (pinfunction "1_1") (pintype "passive"))
      (node (ref "JP15") (pin "2") (pinfunction "2_2") (pintype "passive"))
      (node (ref "JP15") (pin "3") (pinfunction "3_3") (pintype "passive"))
      (node (ref "JP15") (pin "4") (pinfunction "4_4") (pintype "passive"))
      (node (ref "JP18") (pin "1") (pinfunction "1_1") (pintype "passive"))
      (node (ref "JP18") (pin "2") (pinfunction "2_2") (pintype "passive"))
      (node (ref "JP18") (pin "3") (pinfunction "3_3") (pintype "passive"))
      (node (ref "JP18") (pin "4") (pinfunction "4_4") (pintype "passive"))
      (node (ref "JP3") (pin "1") (pinfunction "1_1") (pintype "passive"))
      (node (ref "TP12") (pin "P$1") (pinfunction "P$1_P$1") (pintype "bidirectional"))
      (node (ref "TP13") (pin "P$1") (pinfunction "P$1_P$1") (pintype "bidirectional"))
      (node (ref "U$10") (pin "P$10") (pinfunction "P$10_P$10") (pintype "bidirectional"))
      (node (ref "U$2") (pin "P$1") (pinfunction "P$1_P$1") (pintype "bidirectional"))
      (node (ref "U$2") (pin "P$16") (pinfunction "P$16_P$16") (pintype "bidirectional"))
      (node (ref "U$4") (pin "P$1") (pinfunction "P$1_P$1") (pintype "bidirectional"))
      (node (ref "U$4") (pin "P$16") (pinfunction "P$16_P$16") (pintype "bidirectional"))
      (node (ref "U$5") (pin "P$1") (pinfunction "P$1_P$1") (pintype "bidirectional"))
      (node (ref "U$5") (pin "P$16") (pinfunction "P$16_P$16") (pintype "bidirectional"))
      (node (ref "U$6") (pin "P$1") (pinfunction "P$1_P$1") (pintype "bidirectional"))
      (node (ref "U$6") (pin "P$16") (pinfunction "P$16_P$16") (pintype "bidirectional"))
      (node (ref "U$7") (pin "P$1") (pinfunction "P$1_P$1") (pintype "bidirectional"))
      (node (ref "U$7") (pin "P$16") (pinfunction "P$16_P$16") (pintype "bidirectional"))
      (node (ref "U$8") (pin "P$1") (pinfunction "P$1_P$1") (pintype "bidirectional"))
      (node (ref "U$8") (pin "P$16") (pinfunction "P$16_P$16") (pintype "bidirectional"))
    )
    (net (code "101") (name "/VDD_B") (class "Default")
      (node (ref "C19") (pin "1") (pinfunction "1_1") (pintype "passive"))
      (node (ref "C20") (pin "1") (pinfunction "1_1") (pintype "passive"))
      (node (ref "C21") (pin "2") (pinfunction "2_2") (pintype "passive"))
      (node (ref "C22") (pin "1") (pinfunction "1_1") (pintype "passive"))
      (node (ref "C36") (pin "1") (pinfunction "1_1") (pintype "passive"))
      (node (ref "CONN1") (pin "2") (pinfunction "2_2") (pintype "passive"))
      (node (ref "CONN1") (pin "29") (pinfunction "29_29") (pintype "passive"))
      (node (ref "JP1") (pin "2") (pinfunction "2_2") (pintype "passive"))
      (node (ref "JP1") (pin "4") (pinfunction "4_4") (pintype "passive"))
      (node (ref "JP1") (pin "6") (pinfunction "6_6") (pintype "passive"))
      (node (ref "JP12") (pin "2") (pinfunction "2_2") (pintype "passive"))
      (node (ref "JP9") (pin "1") (pinfunction "1_1") (pintype "passive"))
      (node (ref "JP9") (pin "2") (pinfunction "2_2") (pintype "passive"))
      (node (ref "JP9") (pin "3") (pinfunction "3_3") (pintype "passive"))
      (node (ref "JP9") (pin "4") (pinfunction "4_4") (pintype "passive"))
      (node (ref "R12") (pin "2") (pinfunction "2_2") (pintype "passive"))
      (node (ref "R13") (pin "2") (pinfunction "2_2") (pintype "passive"))
      (node (ref "R17") (pin "2") (pinfunction "2_2") (pintype "passive"))
      (node (ref "TP14") (pin "P$1") (pinfunction "P$1_P$1") (pintype "bidirectional"))
      (node (ref "U4") (pin "11") (pinfunction "AVCC1_11") (pintype "power_in"))
      (node (ref "U4") (pin "15") (pinfunction "DVCC1_15") (pintype "power_in"))
      (node (ref "U4") (pin "40") (pinfunction "DVCC2_40") (pintype "power_in"))
    )
    (net (code "102") (name "/VDD_RADIO") (class "Default")
      (node (ref "JP21") (pin "1") (pinfunction "1_1") (pintype "passive"))
      (node (ref "JP21") (pin "2") (pinfunction "2_2") (pintype "passive"))
      (node (ref "JP21") (pin "3") (pinfunction "3_3") (pintype "passive"))
      (node (ref "JP21") (pin "4") (pinfunction "4_4") (pintype "passive"))
      (node (ref "RADIO_CONN") (pin "P$4") (pinfunction "P$4_P$4") (pintype "bidirectional"))
      (node (ref "TEST") (pin "P$1") (pinfunction "P$1_P$1") (pintype "bidirectional"))
    )
    (net (code "103") (name "/VUSB_EZFET") (class "Default")
      (node (ref "C16") (pin "1") (pinfunction "1_1") (pintype "passive"))
      (node (ref "U3") (pin "54") (pinfunction "54_54") (pintype "power_in"))
    )
    (net (code "104") (name "/V_BUS_USB") (class "Default")
      (node (ref "C3") (pin "1") (pinfunction "1_1") (pintype "passive"))
      (node (ref "C4") (pin "1") (pinfunction "1_1") (pintype "passive"))
      (node (ref "EZUSB") (pin "1") (pinfunction "1_1") (pintype "input"))
      (node (ref "R4") (pin "1") (pinfunction "1_1") (pintype "passive"))
      (node (ref "U1") (pin "1") (pinfunction "IN_1") (pintype "bidirectional"))
      (node (ref "U1") (pin "3") (pinfunction "EN_3") (pintype "bidirectional"))
      (node (ref "U2") (pin "6") (pinfunction "VCC_6") (pintype "power_in"))
      (node (ref "U3") (pin "53") (pinfunction "53_53") (pintype "power_in"))
    )
    (net (code "105") (name "/XIN") (class "Default")
      (node (ref "C24") (pin "1") (pinfunction "1_1") (pintype "passive"))
      (node (ref "U$16") (pin "P$1") (pinfunction "P$1_P$1") (pintype "bidirectional"))
      (node (ref "U4") (pin "12") (pinfunction "P5.4/XIN_12") (pintype "bidirectional"))
    )
    (net (code "106") (name "/XOUT") (class "Default")
      (node (ref "C23") (pin "1") (pinfunction "1_1") (pintype "passive"))
      (node (ref "U$16") (pin "P$2") (pinfunction "P$2_P$2") (pintype "bidirectional"))
      (node (ref "U4") (pin "13") (pinfunction "P5.5/XOUT_13") (pintype "power_in"))
    )
    (net (code "107") (name "/{slash}RST") (class "Default")
      (node (ref "JP12") (pin "13") (pinfunction "13_13") (pintype "passive"))
      (node (ref "JP14") (pin "13") (pinfunction "13_13") (pintype "passive"))
      (node (ref "JP5") (pin "14") (pinfunction "14_14") (pintype "passive"))
      (node (ref "TI_JTAG") (pin "11") (pinfunction "11_11") (pintype "passive"))
    )
    (net (code "108") (name "/{slash}RST_B") (class "Default")
      (node (ref "C17") (pin "1") (pinfunction "1_1") (pintype "passive"))
      (node (ref "CONN1") (pin "19") (pinfunction "19_19") (pintype "passive"))
      (node (ref "JP12") (pin "14") (pinfunction "14_14") (pintype "passive"))
      (node (ref "R17") (pin "1") (pinfunction "1_1") (pintype "passive"))
      (node (ref "S2") (pin "P$1") (pinfunction "P$1_P$1") (pintype "bidirectional"))
      (node (ref "SW3") (pin "P$5") (pinfunction "D_P$5") (pintype "bidirectional"))
      (node (ref "U4") (pin "64") (pinfunction "~{RST/NMI/SBWTDIO}_64") (pintype "bidirectional"))
    )
    (net (code "109") (name "/{slash}RST_BUS") (class "Default")
      (node (ref "CONN2") (pin "19") (pinfunction "19_19") (pintype "passive"))
      (node (ref "CONN3") (pin "19") (pinfunction "19_19") (pintype "passive"))
      (node (ref "JP14") (pin "14") (pinfunction "14_14") (pintype "passive"))
      (node (ref "SW3") (pin "P$6") (pinfunction "E_P$6") (pintype "bidirectional"))
      (node (ref "U$10") (pin "P$4") (pinfunction "P$4_P$4") (pintype "bidirectional"))
      (node (ref "U$2") (pin "P$21") (pinfunction "P$21_P$21") (pintype "bidirectional"))
      (node (ref "U$4") (pin "P$21") (pinfunction "P$21_P$21") (pintype "bidirectional"))
      (node (ref "U$5") (pin "P$21") (pinfunction "P$21_P$21") (pintype "bidirectional"))
      (node (ref "U$6") (pin "P$21") (pinfunction "P$21_P$21") (pintype "bidirectional"))
      (node (ref "U$7") (pin "P$21") (pinfunction "P$21_P$21") (pintype "bidirectional"))
      (node (ref "U$8") (pin "P$21") (pinfunction "P$21_P$21") (pintype "bidirectional"))
    )
    (net (code "110") (name "/{slash}RST_EZFET") (class "Default")
      (node (ref "C5") (pin "1") (pinfunction "1_1") (pintype "passive"))
      (node (ref "JP5") (pin "13") (pinfunction "13_13") (pintype "passive"))
      (node (ref "R2") (pin "1") (pinfunction "1_1") (pintype "passive"))
      (node (ref "S1") (pin "P$2") (pinfunction "P$2_P$2") (pintype "bidirectional"))
      (node (ref "U3") (pin "64") (pinfunction "64_64") (pintype "bidirectional"))
    )
    (net (code "111") (name "GND") (class "Default")
      (node (ref "C1") (pin "2") (pinfunction "2_2") (pintype "passive"))
      (node (ref "C10") (pin "1") (pinfunction "1_1") (pintype "passive"))
      (node (ref "C11") (pin "1") (pinfunction "1_1") (pintype "passive"))
      (node (ref "C12") (pin "1") (pinfunction "1_1") (pintype "passive"))
      (node (ref "C13") (pin "2") (pinfunction "2_2") (pintype "passive"))
      (node (ref "C14") (pin "2") (pinfunction "2_2") (pintype "passive"))
      (node (ref "C15") (pin "2") (pinfunction "2_2") (pintype "passive"))
      (node (ref "C16") (pin "2") (pinfunction "2_2") (pintype "passive"))
      (node (ref "C17") (pin "2") (pinfunction "2_2") (pintype "passive"))
      (node (ref "C18") (pin "2") (pinfunction "2_2") (pintype "passive"))
      (node (ref "C19") (pin "2") (pinfunction "2_2") (pintype "passive"))
      (node (ref "C2") (pin "2") (pinfunction "2_2") (pintype "passive"))
      (node (ref "C20") (pin "2") (pinfunction "2_2") (pintype "passive"))
      (node (ref "C21") (pin "1") (pinfunction "1_1") (pintype "passive"))
      (node (ref "C22") (pin "2") (pinfunction "2_2") (pintype "passive"))
      (node (ref "C23") (pin "2") (pinfunction "2_2") (pintype "passive"))
      (node (ref "C24") (pin "2") (pinfunction "2_2") (pintype "passive"))
      (node (ref "C25") (pin "2") (pinfunction "2_2") (pintype "passive"))
      (node (ref "C26") (pin "1") (pinfunction "1_1") (pintype "passive"))
      (node (ref "C27") (pin "1") (pinfunction "1_1") (pintype "passive"))
      (node (ref "C28") (pin "1") (pinfunction "1_1") (pintype "passive"))
      (node (ref "C29") (pin "1") (pinfunction "1_1") (pintype "passive"))
      (node (ref "C3") (pin "2") (pinfunction "2_2") (pintype "passive"))
      (node (ref "C30") (pin "1") (pinfunction "1_1") (pintype "passive"))
      (node (ref "C31") (pin "1") (pinfunction "1_1") (pintype "passive"))
      (node (ref "C32") (pin "1") (pinfunction "1_1") (pintype "passive"))
      (node (ref "C33") (pin "1") (pinfunction "1_1") (pintype "passive"))
      (node (ref "C36") (pin "2") (pinfunction "2_2") (pintype "passive"))
      (node (ref "C37") (pin "2") (pinfunction "2_2") (pintype "passive"))
      (node (ref "C4") (pin "2") (pinfunction "2_2") (pintype "passive"))
      (node (ref "C5") (pin "2") (pinfunction "2_2") (pintype "passive"))
      (node (ref "C6") (pin "2") (pinfunction "2_2") (pintype "passive"))
      (node (ref "C7") (pin "1") (pinfunction "1_1") (pintype "passive"))
      (node (ref "C8") (pin "1") (pinfunction "1_1") (pintype "passive"))
      (node (ref "C9") (pin "1") (pinfunction "1_1") (pintype "passive"))
      (node (ref "CONN1") (pin "27") (pinfunction "27_27") (pintype "passive"))
      (node (ref "CONN1") (pin "4") (pinfunction "4_4") (pintype "passive"))
      (node (ref "CONN2") (pin "27") (pinfunction "27_27") (pintype "passive"))
      (node (ref "CONN2") (pin "4") (pinfunction "4_4") (pintype "passive"))
      (node (ref "CONN3") (pin "27") (pinfunction "27_27") (pintype "passive"))
      (node (ref "CONN3") (pin "4") (pinfunction "4_4") (pintype "passive"))
      (node (ref "EZUSB") (pin "5") (pinfunction "5_5") (pintype "input"))
      (node (ref "JP10") (pin "1") (pinfunction "1_1") (pintype "passive"))
      (node (ref "JP10") (pin "2") (pinfunction "2_2") (pintype "passive"))
      (node (ref "JP10") (pin "3") (pinfunction "3_3") (pintype "passive"))
      (node (ref "JP10") (pin "4") (pinfunction "4_4") (pintype "passive"))
      (node (ref "JP16") (pin "7") (pinfunction "7_7") (pintype "passive"))
      (node (ref "JP19") (pin "1") (pinfunction "1_1") (pintype "passive"))
      (node (ref "JP19") (pin "2") (pinfunction "2_2") (pintype "passive"))
      (node (ref "JP19") (pin "3") (pinfunction "3_3") (pintype "passive"))
      (node (ref "JP19") (pin "4") (pinfunction "4_4") (pintype "passive"))
      (node (ref "JP6") (pin "3") (pinfunction "3_3") (pintype "passive"))
      (node (ref "JP8") (pin "10") (pinfunction "10_10") (pintype "passive"))
      (node (ref "JP8") (pin "12") (pinfunction "12_12") (pintype "passive"))
      (node (ref "JP8") (pin "14") (pinfunction "14_14") (pintype "passive"))
      (node (ref "JP8") (pin "2") (pinfunction "2_2") (pintype "passive"))
      (node (ref "JP8") (pin "4") (pinfunction "4_4") (pintype "passive"))
      (node (ref "JP8") (pin "6") (pinfunction "6_6") (pintype "passive"))
      (node (ref "JP8") (pin "8") (pinfunction "8_8") (pintype "passive"))
      (node (ref "LED1") (pin "C") (pinfunction "C_C") (pintype "passive"))
      (node (ref "LED2") (pin "C") (pinfunction "C_C") (pintype "passive"))
      (node (ref "LED3") (pin "C") (pinfunction "C_C") (pintype "passive"))
      (node (ref "Q2") (pin "2") (pinfunction "2_2") (pintype "passive"))
      (node (ref "R16") (pin "2") (pinfunction "2_2") (pintype "passive"))
      (node (ref "R21") (pin "2") (pinfunction "2_2") (pintype "passive"))
      (node (ref "R3") (pin "1") (pinfunction "1_1") (pintype "passive"))
      (node (ref "R6") (pin "2") (pinfunction "2_2") (pintype "passive"))
      (node (ref "R7") (pin "2") (pinfunction "2_2") (pintype "passive"))
      (node (ref "RADIO_CONN") (pin "P$5") (pinfunction "P$5_P$5") (pintype "bidirectional"))
      (node (ref "S1") (pin "P$1") (pinfunction "P$1_P$1") (pintype "bidirectional"))
      (node (ref "S2") (pin "P$2") (pinfunction "P$2_P$2") (pintype "bidirectional"))
      (node (ref "TI_JTAG") (pin "9") (pinfunction "9_9") (pintype "passive"))
      (node (ref "TP1") (pin "P$1") (pinfunction "P$1_P$1") (pintype "bidirectional"))
      (node (ref "TP10") (pin "P$1") (pinfunction "P$1_P$1") (pintype "bidirectional"))
      (node (ref "TP11") (pin "P$1") (pinfunction "P$1_P$1") (pintype "bidirectional"))
      (node (ref "TP4") (pin "P$1") (pinfunction "P$1_P$1") (pintype "bidirectional"))
      (node (ref "TP5") (pin "P$1") (pinfunction "P$1_P$1") (pintype "bidirectional"))
      (node (ref "TP6") (pin "P$1") (pinfunction "P$1_P$1") (pintype "bidirectional"))
      (node (ref "TP7") (pin "P$1") (pinfunction "P$1_P$1") (pintype "bidirectional"))
      (node (ref "TP8") (pin "P$1") (pinfunction "P$1_P$1") (pintype "bidirectional"))
      (node (ref "TP9") (pin "P$1") (pinfunction "P$1_P$1") (pintype "bidirectional"))
      (node (ref "U$10") (pin "P$1") (pinfunction "P$1_P$1") (pintype "bidirectional"))
      (node (ref "U$2") (pin "P$17") (pinfunction "P$17_P$17") (pintype "bidirectional"))
      (node (ref "U$2") (pin "P$2") (pinfunction "P$2_P$2") (pintype "bidirectional"))
      (node (ref "U$4") (pin "P$17") (pinfunction "P$17_P$17") (pintype "bidirectional"))
      (node (ref "U$4") (pin "P$2") (pinfunction "P$2_P$2") (pintype "bidirectional"))
      (node (ref "U$5") (pin "P$17") (pinfunction "P$17_P$17") (pintype "bidirectional"))
      (node (ref "U$5") (pin "P$2") (pinfunction "P$2_P$2") (pintype "bidirectional"))
      (node (ref "U$6") (pin "P$17") (pinfunction "P$17_P$17") (pintype "bidirectional"))
      (node (ref "U$6") (pin "P$2") (pinfunction "P$2_P$2") (pintype "bidirectional"))
      (node (ref "U$7") (pin "P$17") (pinfunction "P$17_P$17") (pintype "bidirectional"))
      (node (ref "U$7") (pin "P$2") (pinfunction "P$2_P$2") (pintype "bidirectional"))
      (node (ref "U$8") (pin "P$17") (pinfunction "P$17_P$17") (pintype "bidirectional"))
      (node (ref "U$8") (pin "P$2") (pinfunction "P$2_P$2") (pintype "bidirectional"))
      (node (ref "U$9") (pin "P$17") (pinfunction "P$17_P$17") (pintype "bidirectional"))
      (node (ref "U$9") (pin "P$2") (pinfunction "P$2_P$2") (pintype "bidirectional"))
      (node (ref "U1") (pin "2") (pinfunction "GND_2") (pintype "bidirectional"))
      (node (ref "U2") (pin "3") (pinfunction "GND_3") (pintype "power_in"))
      (node (ref "U3") (pin "14") (pinfunction "14_14") (pintype "power_in"))
      (node (ref "U3") (pin "16") (pinfunction "16_16") (pintype "power_in"))
      (node (ref "U3") (pin "39") (pinfunction "39_39") (pintype "power_in"))
      (node (ref "U3") (pin "49") (pinfunction "49_49") (pintype "power_in"))
      (node (ref "U3") (pin "56") (pinfunction "56_56") (pintype "power_in"))
      (node (ref "U3") (pin "TP") (pinfunction "TP_TP") (pintype "power_in"))
      (node (ref "U4") (pin "14") (pinfunction "AVSS1_14") (pintype "power_in"))
      (node (ref "U4") (pin "16") (pinfunction "DVSS1_16") (pintype "power_in"))
      (node (ref "U4") (pin "39") (pinfunction "DVSS2_39") (pintype "power_in"))
      (node (ref "U4") (pin "49") (pinfunction "VSSU_49") (pintype "power_in"))
      (node (ref "U4") (pin "53") (pinfunction "VBUS_53") (pintype "power_in"))
      (node (ref "U4") (pin "56") (pinfunction "AVSS2_56") (pintype "power_in"))
      (node (ref "U4") (pin "65") (pinfunction "EPAD_65") (pintype "passive"))
    )
    (net (code "112") (name "Net-(C2-Pad1)") (class "Default")
      (node (ref "C2") (pin "1") (pinfunction "1_1") (pintype "passive"))
      (node (ref "U3") (pin "17") (pinfunction "17_17") (pintype "power_in"))
    )
    (net (code "113") (name "Net-(JP4-Pad1)") (class "Default")
      (node (ref "JP4") (pin "1") (pinfunction "1_1") (pintype "passive"))
      (node (ref "R13") (pin "1") (pinfunction "1_1") (pintype "passive"))
    )
    (net (code "114") (name "Net-(JP4-Pad3)") (class "Default")
      (node (ref "JP4") (pin "3") (pinfunction "3_3") (pintype "passive"))
      (node (ref "R12") (pin "1") (pinfunction "1_1") (pintype "passive"))
    )
    (net (code "115") (name "Net-(LED1-PadA)") (class "Default")
      (node (ref "LED1") (pin "A") (pinfunction "A_A") (pintype "passive"))
      (node (ref "R10") (pin "1") (pinfunction "1_1") (pintype "passive"))
    )
    (net (code "116") (name "Net-(LED2-PadA)") (class "Default")
      (node (ref "LED2") (pin "A") (pinfunction "A_A") (pintype "passive"))
      (node (ref "R11") (pin "1") (pinfunction "1_1") (pintype "passive"))
    )
    (net (code "117") (name "Net-(LED3-PadA)") (class "Default")
      (node (ref "LED3") (pin "A") (pinfunction "A_A") (pintype "passive"))
      (node (ref "R14") (pin "1") (pinfunction "1_1") (pintype "passive"))
    )
    (net (code "118") (name "Net-(Q2-Pad1)") (class "Default")
      (node (ref "Q2") (pin "1") (pinfunction "1_1") (pintype "passive"))
      (node (ref "U3") (pin "57") (pinfunction "57_57") (pintype "bidirectional"))
    )
    (net (code "119") (name "Net-(Q2-Pad3)") (class "Default")
      (node (ref "Q2") (pin "3") (pinfunction "3_3") (pintype "passive"))
      (node (ref "U3") (pin "58") (pinfunction "58_58") (pintype "bidirectional"))
    )
    (net (code "120") (name "Net-(SW3-COM1)") (class "Default")
      (node (ref "R15") (pin "1") (pinfunction "1_1") (pintype "passive"))
      (node (ref "SW3") (pin "P$3") (pinfunction "COM1_P$3") (pintype "bidirectional"))
    )
    (net (code "121") (name "Net-(SW3-COM2)") (class "Default")
      (node (ref "R18") (pin "2") (pinfunction "2_2") (pintype "passive"))
      (node (ref "SW3") (pin "P$7") (pinfunction "COM2_P$7") (pintype "bidirectional"))
    )
    (net (code "122") (name "Net-(SW4-COM1)") (class "Default")
      (node (ref "R20") (pin "1") (pinfunction "1_1") (pintype "passive"))
      (node (ref "SW4") (pin "P$3") (pinfunction "COM1_P$3") (pintype "bidirectional"))
    )
    (net (code "123") (name "Net-(SW4-COM2)") (class "Default")
      (node (ref "R19") (pin "1") (pinfunction "1_1") (pintype "passive"))
      (node (ref "SW4") (pin "P$7") (pinfunction "COM2_P$7") (pintype "bidirectional"))
    )
    (net (code "124") (name "Net-(U1-NR)") (class "Default")
      (node (ref "C1") (pin "1") (pinfunction "1_1") (pintype "passive"))
      (node (ref "U1") (pin "4") (pinfunction "NR_4") (pintype "bidirectional"))
    )
    (net (code "125") (name "Net-(U4-PUR)") (class "Default")
      (node (ref "R16") (pin "1") (pinfunction "1_1") (pintype "passive"))
      (node (ref "U4") (pin "51") (pinfunction "PUR_51") (pintype "bidirectional"))
    )
    (net (code "126") (name "Net-(U4-VCORE)") (class "Default")
      (node (ref "C18") (pin "1") (pinfunction "1_1") (pintype "passive"))
      (node (ref "U4") (pin "17") (pinfunction "VCORE_17") (pintype "power_in"))
    )
    (net (code "127") (name "unconnected-(EZUSB-Pad4)") (class "Default")
      (node (ref "EZUSB") (pin "4") (pinfunction "4_4") (pintype "input"))
    )
    (net (code "128") (name "unconnected-(JP16-Pad6)") (class "Default")
      (node (ref "JP16") (pin "6") (pinfunction "6_6") (pintype "passive"))
    )
    (net (code "129") (name "unconnected-(RADIO_CONN-PadP$3)") (class "Default")
      (node (ref "RADIO_CONN") (pin "P$3") (pinfunction "P$3_P$3") (pintype "bidirectional"))
    )
    (net (code "130") (name "unconnected-(RADIO_CONN-PadP$11)") (class "Default")
      (node (ref "RADIO_CONN") (pin "P$11") (pinfunction "P$11_P$11") (pintype "bidirectional"))
    )
    (net (code "131") (name "unconnected-(RADIO_CONN-PadP$12)") (class "Default")
      (node (ref "RADIO_CONN") (pin "P$12") (pinfunction "P$12_P$12") (pintype "bidirectional"))
    )
    (net (code "132") (name "unconnected-(RADIO_CONN-PadP$13)") (class "Default")
      (node (ref "RADIO_CONN") (pin "P$13") (pinfunction "P$13_P$13") (pintype "bidirectional"))
    )
    (net (code "133") (name "unconnected-(RADIO_CONN-PadP$14)") (class "Default")
      (node (ref "RADIO_CONN") (pin "P$14") (pinfunction "P$14_P$14") (pintype "bidirectional"))
    )
    (net (code "134") (name "unconnected-(SW1-B-PadP$2)") (class "Default")
      (node (ref "SW1") (pin "P$2") (pinfunction "B_P$2") (pintype "bidirectional"))
    )
    (net (code "135") (name "unconnected-(SW1-C-PadP$4)") (class "Default")
      (node (ref "SW1") (pin "P$4") (pinfunction "C_P$4") (pintype "bidirectional"))
    )
    (net (code "136") (name "unconnected-(SW1-E-PadP$6)") (class "Default")
      (node (ref "SW1") (pin "P$6") (pinfunction "E_P$6") (pintype "bidirectional"))
    )
    (net (code "137") (name "unconnected-(SW1-F-PadP$8)") (class "Default")
      (node (ref "SW1") (pin "P$8") (pinfunction "F_P$8") (pintype "bidirectional"))
    )
    (net (code "138") (name "unconnected-(SW2-B-PadP$2)") (class "Default")
      (node (ref "SW2") (pin "P$2") (pinfunction "B_P$2") (pintype "bidirectional"))
    )
    (net (code "139") (name "unconnected-(SW2-C-PadP$4)") (class "Default")
      (node (ref "SW2") (pin "P$4") (pinfunction "C_P$4") (pintype "bidirectional"))
    )
    (net (code "140") (name "unconnected-(SW2-E-PadP$6)") (class "Default")
      (node (ref "SW2") (pin "P$6") (pinfunction "E_P$6") (pintype "bidirectional"))
    )
    (net (code "141") (name "unconnected-(SW2-F-PadP$8)") (class "Default")
      (node (ref "SW2") (pin "P$8") (pinfunction "F_P$8") (pintype "bidirectional"))
    )
    (net (code "142") (name "unconnected-(SW3-C-PadP$4)") (class "Default")
      (node (ref "SW3") (pin "P$4") (pinfunction "C_P$4") (pintype "bidirectional"))
    )
    (net (code "143") (name "unconnected-(SW3-F-PadP$8)") (class "Default")
      (node (ref "SW3") (pin "P$8") (pinfunction "F_P$8") (pintype "bidirectional"))
    )
    (net (code "144") (name "unconnected-(SW4-C-PadP$4)") (class "Default")
      (node (ref "SW4") (pin "P$4") (pinfunction "C_P$4") (pintype "bidirectional"))
    )
    (net (code "145") (name "unconnected-(SW4-F-PadP$8)") (class "Default")
      (node (ref "SW4") (pin "P$8") (pinfunction "F_P$8") (pintype "bidirectional"))
    )
    (net (code "146") (name "unconnected-(TI_JTAG-Pad6)") (class "Default")
      (node (ref "TI_JTAG") (pin "6") (pinfunction "6_6") (pintype "passive"))
    )
    (net (code "147") (name "unconnected-(TI_JTAG-Pad10)") (class "Default")
      (node (ref "TI_JTAG") (pin "10") (pinfunction "10_10") (pintype "passive"))
    )
    (net (code "148") (name "unconnected-(TI_JTAG-Pad12)") (class "Default")
      (node (ref "TI_JTAG") (pin "12") (pinfunction "12_12") (pintype "passive"))
    )
    (net (code "149") (name "unconnected-(TI_JTAG-Pad13)") (class "Default")
      (node (ref "TI_JTAG") (pin "13") (pinfunction "13_13") (pintype "passive"))
    )
    (net (code "150") (name "unconnected-(TI_JTAG-Pad14)") (class "Default")
      (node (ref "TI_JTAG") (pin "14") (pinfunction "14_14") (pintype "passive"))
    )
    (net (code "151") (name "unconnected-(U$9-PadP$3)") (class "Default")
      (node (ref "U$9") (pin "P$3") (pinfunction "P$3_P$3") (pintype "bidirectional"))
    )
    (net (code "152") (name "unconnected-(U$9-PadP$4)") (class "Default")
      (node (ref "U$9") (pin "P$4") (pinfunction "P$4_P$4") (pintype "bidirectional"))
    )
    (net (code "153") (name "unconnected-(U$9-PadP$5)") (class "Default")
      (node (ref "U$9") (pin "P$5") (pinfunction "P$5_P$5") (pintype "bidirectional"))
    )
    (net (code "154") (name "unconnected-(U$9-PadP$6)") (class "Default")
      (node (ref "U$9") (pin "P$6") (pinfunction "P$6_P$6") (pintype "bidirectional"))
    )
    (net (code "155") (name "unconnected-(U$9-PadP$7)") (class "Default")
      (node (ref "U$9") (pin "P$7") (pinfunction "P$7_P$7") (pintype "bidirectional"))
    )
    (net (code "156") (name "unconnected-(U$9-PadP$8)") (class "Default")
      (node (ref "U$9") (pin "P$8") (pinfunction "P$8_P$8") (pintype "bidirectional"))
    )
    (net (code "157") (name "unconnected-(U$9-PadP$11)") (class "Default")
      (node (ref "U$9") (pin "P$11") (pinfunction "P$11_P$11") (pintype "bidirectional"))
    )
    (net (code "158") (name "unconnected-(U$9-PadP$12)") (class "Default")
      (node (ref "U$9") (pin "P$12") (pinfunction "P$12_P$12") (pintype "bidirectional"))
    )
    (net (code "159") (name "unconnected-(U$9-PadP$13)") (class "Default")
      (node (ref "U$9") (pin "P$13") (pinfunction "P$13_P$13") (pintype "bidirectional"))
    )
    (net (code "160") (name "unconnected-(U$9-PadP$14)") (class "Default")
      (node (ref "U$9") (pin "P$14") (pinfunction "P$14_P$14") (pintype "bidirectional"))
    )
    (net (code "161") (name "unconnected-(U$9-PadP$15)") (class "Default")
      (node (ref "U$9") (pin "P$15") (pinfunction "P$15_P$15") (pintype "bidirectional"))
    )
    (net (code "162") (name "unconnected-(U$9-PadP$18)") (class "Default")
      (node (ref "U$9") (pin "P$18") (pinfunction "P$18_P$18") (pintype "bidirectional"))
    )
    (net (code "163") (name "unconnected-(U$9-PadP$19)") (class "Default")
      (node (ref "U$9") (pin "P$19") (pinfunction "P$19_P$19") (pintype "bidirectional"))
    )
    (net (code "164") (name "unconnected-(U$9-PadP$20)") (class "Default")
      (node (ref "U$9") (pin "P$20") (pinfunction "P$20_P$20") (pintype "bidirectional"))
    )
    (net (code "165") (name "unconnected-(U$9-PadP$21)") (class "Default")
      (node (ref "U$9") (pin "P$21") (pinfunction "P$21_P$21") (pintype "bidirectional"))
    )
    (net (code "166") (name "unconnected-(U$9-PadP$22)") (class "Default")
      (node (ref "U$9") (pin "P$22") (pinfunction "P$22_P$22") (pintype "bidirectional"))
    )
    (net (code "167") (name "unconnected-(U$9-PadP$23)") (class "Default")
      (node (ref "U$9") (pin "P$23") (pinfunction "P$23_P$23") (pintype "bidirectional"))
    )
    (net (code "168") (name "unconnected-(U$9-PadP$24)") (class "Default")
      (node (ref "U$9") (pin "P$24") (pinfunction "P$24_P$24") (pintype "bidirectional"))
    )
    (net (code "169") (name "unconnected-(U$9-PadP$25)") (class "Default")
      (node (ref "U$9") (pin "P$25") (pinfunction "P$25_P$25") (pintype "bidirectional"))
    )
    (net (code "170") (name "unconnected-(U$9-PadP$26)") (class "Default")
      (node (ref "U$9") (pin "P$26") (pinfunction "P$26_P$26") (pintype "bidirectional"))
    )
    (net (code "171") (name "unconnected-(U$9-PadP$27)") (class "Default")
      (node (ref "U$9") (pin "P$27") (pinfunction "P$27_P$27") (pintype "bidirectional"))
    )
    (net (code "172") (name "unconnected-(U$9-PadP$28)") (class "Default")
      (node (ref "U$9") (pin "P$28") (pinfunction "P$28_P$28") (pintype "bidirectional"))
    )
    (net (code "173") (name "unconnected-(U$9-PadP$29)") (class "Default")
      (node (ref "U$9") (pin "P$29") (pinfunction "P$29_P$29") (pintype "bidirectional"))
    )
    (net (code "174") (name "unconnected-(U$9-PadP$30)") (class "Default")
      (node (ref "U$9") (pin "P$30") (pinfunction "P$30_P$30") (pintype "bidirectional"))
    )
    (net (code "175") (name "unconnected-(U$10-PadP$2)") (class "Default")
      (node (ref "U$10") (pin "P$2") (pinfunction "P$2_P$2") (pintype "bidirectional"))
    )
    (net (code "176") (name "unconnected-(U$10-PadP$3)") (class "Default")
      (node (ref "U$10") (pin "P$3") (pinfunction "P$3_P$3") (pintype "bidirectional"))
    )
    (net (code "177") (name "unconnected-(U2-IO2-Pad2)") (class "Default")
      (node (ref "U2") (pin "2") (pinfunction "IO2_2") (pintype "bidirectional"))
    )
    (net (code "178") (name "unconnected-(U3-Pad3)") (class "Default")
      (node (ref "U3") (pin "3") (pinfunction "3_3") (pintype "bidirectional"))
    )
    (net (code "179") (name "unconnected-(U3-Pad4)") (class "Default")
      (node (ref "U3") (pin "4") (pinfunction "4_4") (pintype "bidirectional"))
    )
    (net (code "180") (name "unconnected-(U3-Pad5)") (class "Default")
      (node (ref "U3") (pin "5") (pinfunction "5_5") (pintype "bidirectional"))
    )
    (net (code "181") (name "unconnected-(U3-Pad6)") (class "Default")
      (node (ref "U3") (pin "6") (pinfunction "6_6") (pintype "bidirectional"))
    )
    (net (code "182") (name "unconnected-(U3-Pad7)") (class "Default")
      (node (ref "U3") (pin "7") (pinfunction "7_7") (pintype "no_connect"))
    )
    (net (code "183") (name "unconnected-(U3-Pad8)") (class "Default")
      (node (ref "U3") (pin "8") (pinfunction "8_8") (pintype "input"))
    )
    (net (code "184") (name "unconnected-(U3-Pad10)") (class "Default")
      (node (ref "U3") (pin "10") (pinfunction "10_10") (pintype "bidirectional"))
    )
    (net (code "185") (name "unconnected-(U3-Pad12)") (class "Default")
      (node (ref "U3") (pin "12") (pinfunction "12_12") (pintype "bidirectional"))
    )
    (net (code "186") (name "unconnected-(U3-Pad13)") (class "Default")
      (node (ref "U3") (pin "13") (pinfunction "13_13") (pintype "bidirectional"))
    )
    (net (code "187") (name "unconnected-(U3-Pad18)") (class "Default")
      (node (ref "U3") (pin "18") (pinfunction "18_18") (pintype "bidirectional"))
    )
    (net (code "188") (name "unconnected-(U3-Pad19)") (class "Default")
      (node (ref "U3") (pin "19") (pinfunction "19_19") (pintype "bidirectional"))
    )
    (net (code "189") (name "unconnected-(U3-Pad22)") (class "Default")
      (node (ref "U3") (pin "22") (pinfunction "22_22") (pintype "bidirectional"))
    )
    (net (code "190") (name "unconnected-(U3-Pad23)") (class "Default")
      (node (ref "U3") (pin "23") (pinfunction "23_23") (pintype "bidirectional"))
    )
    (net (code "191") (name "unconnected-(U3-Pad24)") (class "Default")
      (node (ref "U3") (pin "24") (pinfunction "24_24") (pintype "bidirectional"))
    )
    (net (code "192") (name "unconnected-(U3-Pad25)") (class "Default")
      (node (ref "U3") (pin "25") (pinfunction "25_25") (pintype "bidirectional"))
    )
    (net (code "193") (name "unconnected-(U3-Pad26)") (class "Default")
      (node (ref "U3") (pin "26") (pinfunction "26_26") (pintype "bidirectional"))
    )
    (net (code "194") (name "unconnected-(U3-Pad27)") (class "Default")
      (node (ref "U3") (pin "27") (pinfunction "27_27") (pintype "bidirectional"))
    )
    (net (code "195") (name "unconnected-(U3-Pad28)") (class "Default")
      (node (ref "U3") (pin "28") (pinfunction "28_28") (pintype "bidirectional"))
    )
    (net (code "196") (name "unconnected-(U3-Pad29)") (class "Default")
      (node (ref "U3") (pin "29") (pinfunction "29_29") (pintype "bidirectional"))
    )
    (net (code "197") (name "unconnected-(U3-Pad30)") (class "Default")
      (node (ref "U3") (pin "30") (pinfunction "30_30") (pintype "bidirectional"))
    )
    (net (code "198") (name "unconnected-(U3-Pad31)") (class "Default")
      (node (ref "U3") (pin "31") (pinfunction "31_31") (pintype "bidirectional"))
    )
    (net (code "199") (name "unconnected-(U3-Pad32)") (class "Default")
      (node (ref "U3") (pin "32") (pinfunction "32_32") (pintype "bidirectional"))
    )
    (net (code "200") (name "unconnected-(U3-Pad33)") (class "Default")
      (node (ref "U3") (pin "33") (pinfunction "33_33") (pintype "bidirectional"))
    )
    (net (code "201") (name "unconnected-(U3-Pad34)") (class "Default")
      (node (ref "U3") (pin "34") (pinfunction "34_34") (pintype "bidirectional"))
    )
    (net (code "202") (name "unconnected-(U3-Pad35)") (class "Default")
      (node (ref "U3") (pin "35") (pinfunction "35_35") (pintype "bidirectional"))
    )
    (net (code "203") (name "unconnected-(U3-Pad36)") (class "Default")
      (node (ref "U3") (pin "36") (pinfunction "36_36") (pintype "bidirectional"))
    )
    (net (code "204") (name "unconnected-(U3-Pad41)") (class "Default")
      (node (ref "U3") (pin "41") (pinfunction "41_41") (pintype "bidirectional"))
    )
    (net (code "205") (name "unconnected-(U3-Pad42)") (class "Default")
      (node (ref "U3") (pin "42") (pinfunction "42_42") (pintype "bidirectional"))
    )
    (net (code "206") (name "unconnected-(U3-Pad46)") (class "Default")
      (node (ref "U3") (pin "46") (pinfunction "46_46") (pintype "bidirectional"))
    )
    (net (code "207") (name "unconnected-(U3-Pad47)") (class "Default")
      (node (ref "U3") (pin "47") (pinfunction "47_47") (pintype "bidirectional"))
    )
    (net (code "208") (name "unconnected-(U3-Pad48)") (class "Default")
      (node (ref "U3") (pin "48") (pinfunction "48_48") (pintype "bidirectional"))
    )
    (net (code "209") (name "unconnected-(U4-P1.1{slash}TA0.0-Pad19)") (class "Default")
      (node (ref "U4") (pin "19") (pinfunction "P1.1/TA0.0_19") (pintype "bidirectional"))
    )
    (net (code "210") (name "unconnected-(U4-P1.6{slash}TA1CLK{slash}CBOUT-Pad24)") (class "Default")
      (node (ref "U4") (pin "24") (pinfunction "P1.6/TA1CLK/CBOUT_24") (pintype "bidirectional"))
    )
    (net (code "211") (name "unconnected-(U4-P2.0{slash}TA1.1-Pad26)") (class "Default")
      (node (ref "U4") (pin "26") (pinfunction "P2.0/TA1.1_26") (pintype "bidirectional"))
    )
    (net (code "212") (name "unconnected-(U4-P2.2{slash}TA2CLK{slash}SMCLK-Pad28)") (class "Default")
      (node (ref "U4") (pin "28") (pinfunction "P2.2/TA2CLK/SMCLK_28") (pintype "bidirectional"))
    )
    (net (code "213") (name "unconnected-(U4-P2.5{slash}TA2.2-Pad31)") (class "Default")
      (node (ref "U4") (pin "31") (pinfunction "P2.5/TA2.2_31") (pintype "bidirectional"))
    )
    (net (code "214") (name "unconnected-(U4-P2.6{slash}RTCCLK{slash}DMAE0-Pad32)") (class "Default")
      (node (ref "U4") (pin "32") (pinfunction "P2.6/RTCCLK/DMAE0_32") (pintype "bidirectional"))
    )
    (net (code "215") (name "unconnected-(U4-P4.3{slash}PM_UCB1CLK{slash}PM_UCA1STE-Pad44)") (class "Default")
      (node (ref "U4") (pin "44") (pinfunction "P4.3/PM_UCB1CLK/PM_UCA1STE_44") (pintype "bidirectional"))
    )
    (net (code "216") (name "unconnected-(U4-P5.0{slash}A8{slash}VREF+{slash}VEREF+-Pad9)") (class "Default")
      (node (ref "U4") (pin "9") (pinfunction "P5.0/A8/VREF+/VEREF+_9") (pintype "bidirectional"))
    )
    (net (code "217") (name "unconnected-(U4-P5.1{slash}A9{slash}VREF-{slash}VEREF--Pad10)") (class "Default")
      (node (ref "U4") (pin "10") (pinfunction "P5.1/A9/VREF-/VEREF-_10") (pintype "bidirectional"))
    )
    (net (code "218") (name "unconnected-(U4-P6.1{slash}CB1{slash}A1-Pad2)") (class "Default")
      (node (ref "U4") (pin "2") (pinfunction "P6.1/CB1/A1_2") (pintype "bidirectional"))
    )
    (net (code "219") (name "unconnected-(U4-P6.3{slash}CB3{slash}A3-Pad4)") (class "Default")
      (node (ref "U4") (pin "4") (pinfunction "P6.3/CB3/A3_4") (pintype "bidirectional"))
    )
    (net (code "220") (name "unconnected-(U4-P6.4{slash}CB4{slash}A4-Pad5)") (class "Default")
      (node (ref "U4") (pin "5") (pinfunction "P6.4/CB4/A4_5") (pintype "bidirectional"))
    )
    (net (code "221") (name "unconnected-(U4-P6.5{slash}CB5{slash}A5-Pad6)") (class "Default")
      (node (ref "U4") (pin "6") (pinfunction "P6.5/CB5/A5_6") (pintype "bidirectional"))
    )
    (net (code "222") (name "unconnected-(U4-P6.7{slash}CB7{slash}A7-Pad8)") (class "Default")
      (node (ref "U4") (pin "8") (pinfunction "P6.7/CB7/A7_8") (pintype "bidirectional"))
    )
    (net (code "223") (name "unconnected-(U4-PU.0{slash}DP-Pad50)") (class "Default")
      (node (ref "U4") (pin "50") (pinfunction "PU.0/DP_50") (pintype "bidirectional"))
    )
    (net (code "224") (name "unconnected-(U4-PU.1{slash}DM-Pad52)") (class "Default")
      (node (ref "U4") (pin "52") (pinfunction "PU.1/DM_52") (pintype "bidirectional"))
    )
    (net (code "225") (name "unconnected-(U4-VUSB-Pad54)") (class "Default")
      (node (ref "U4") (pin "54") (pinfunction "VUSB_54") (pintype "output"))
    )
  )
)
